# sucaiku.net
KiCad netlist of a schematic drawn in EasyEDA Pro
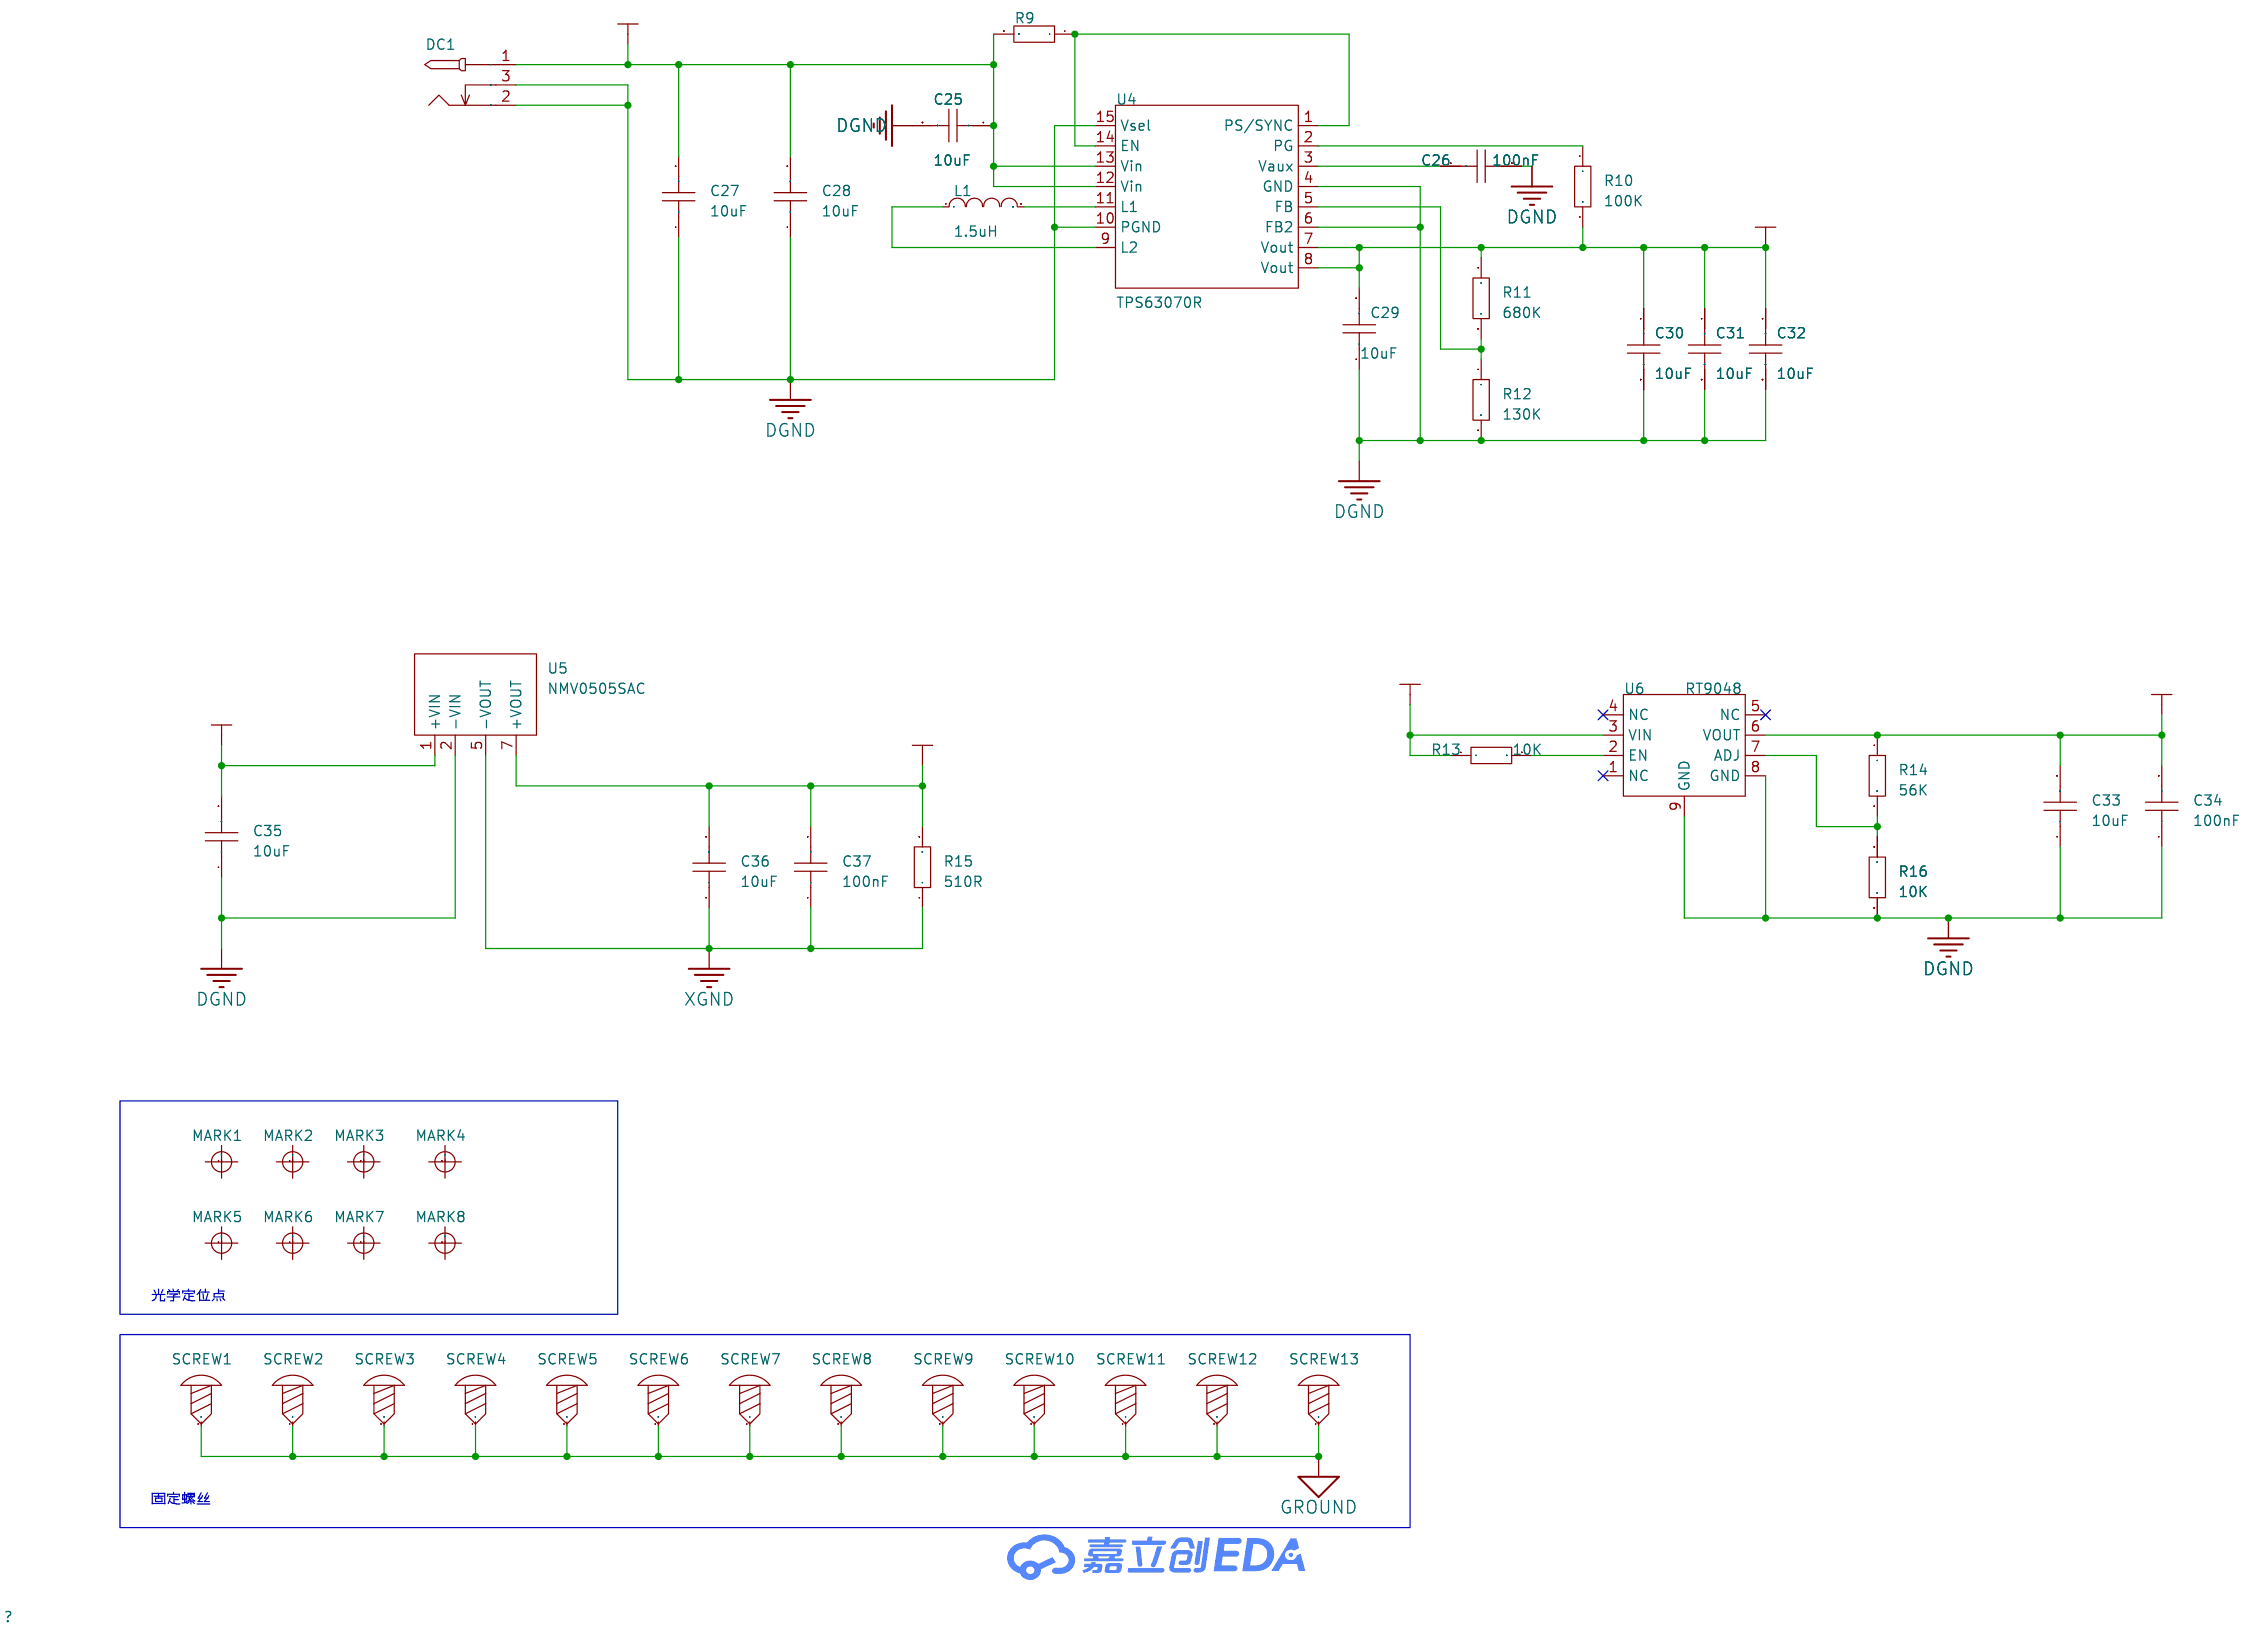
[diagram p0: POWER]
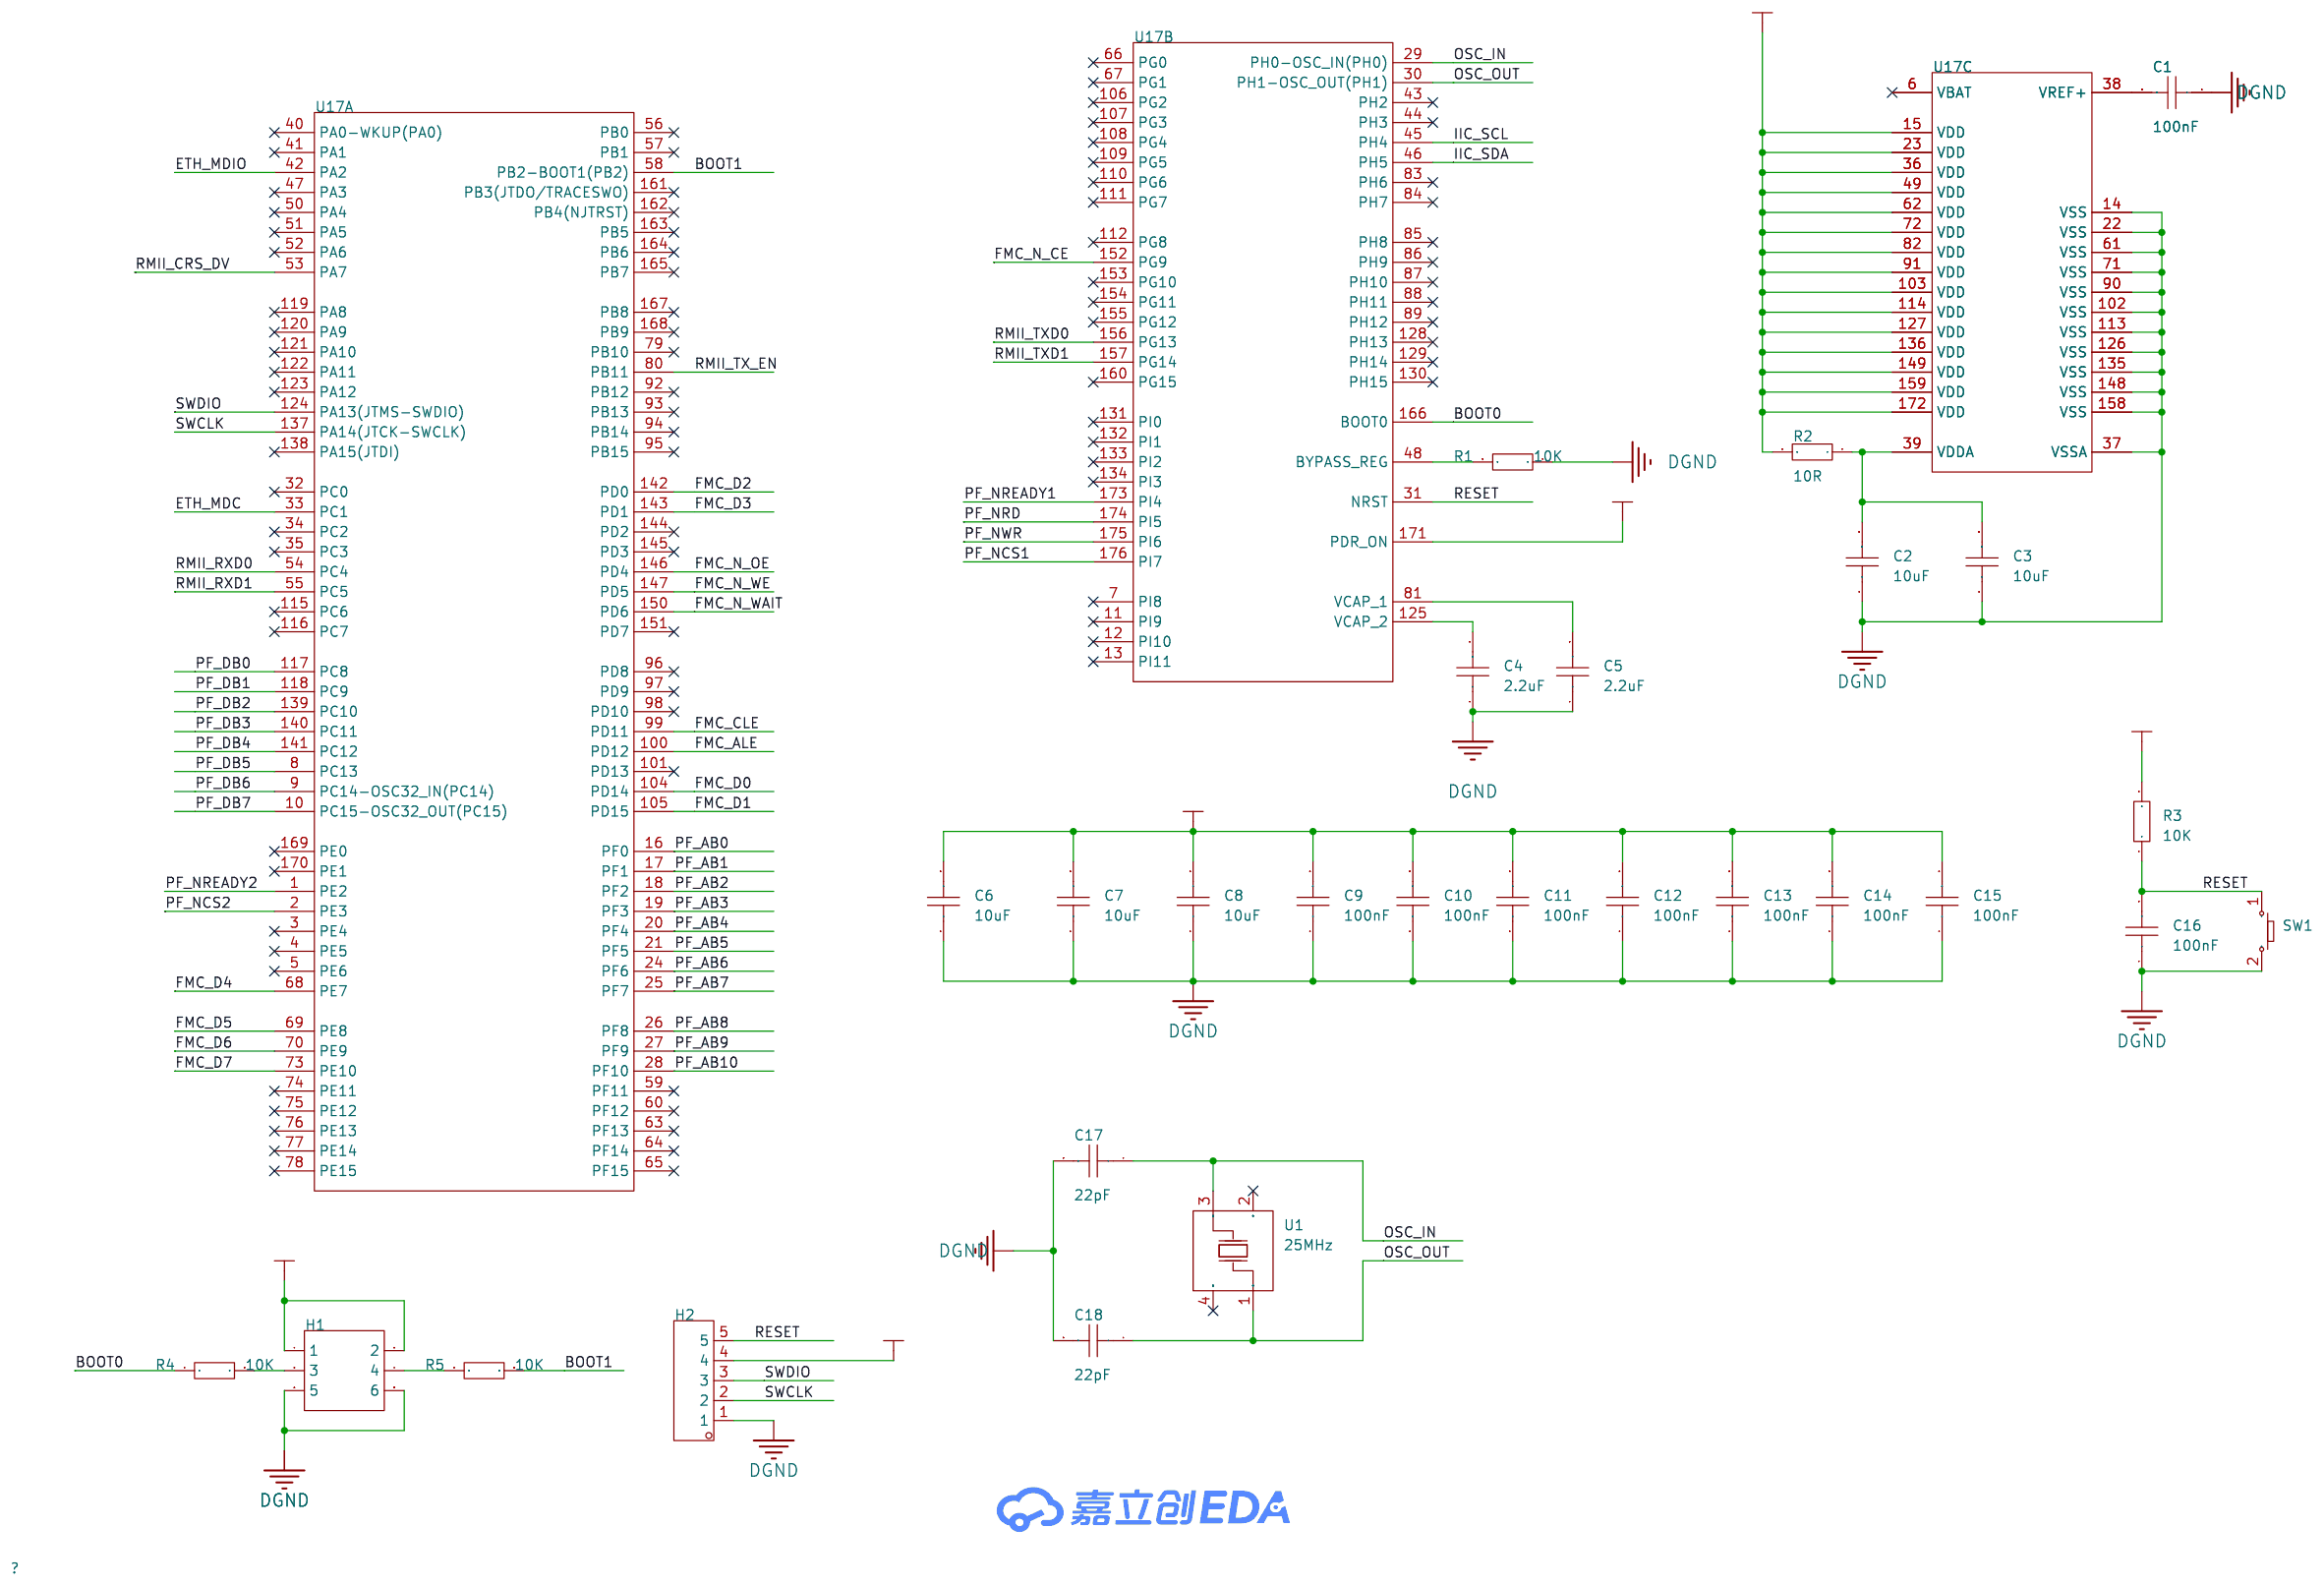
[diagram p1: MCU]
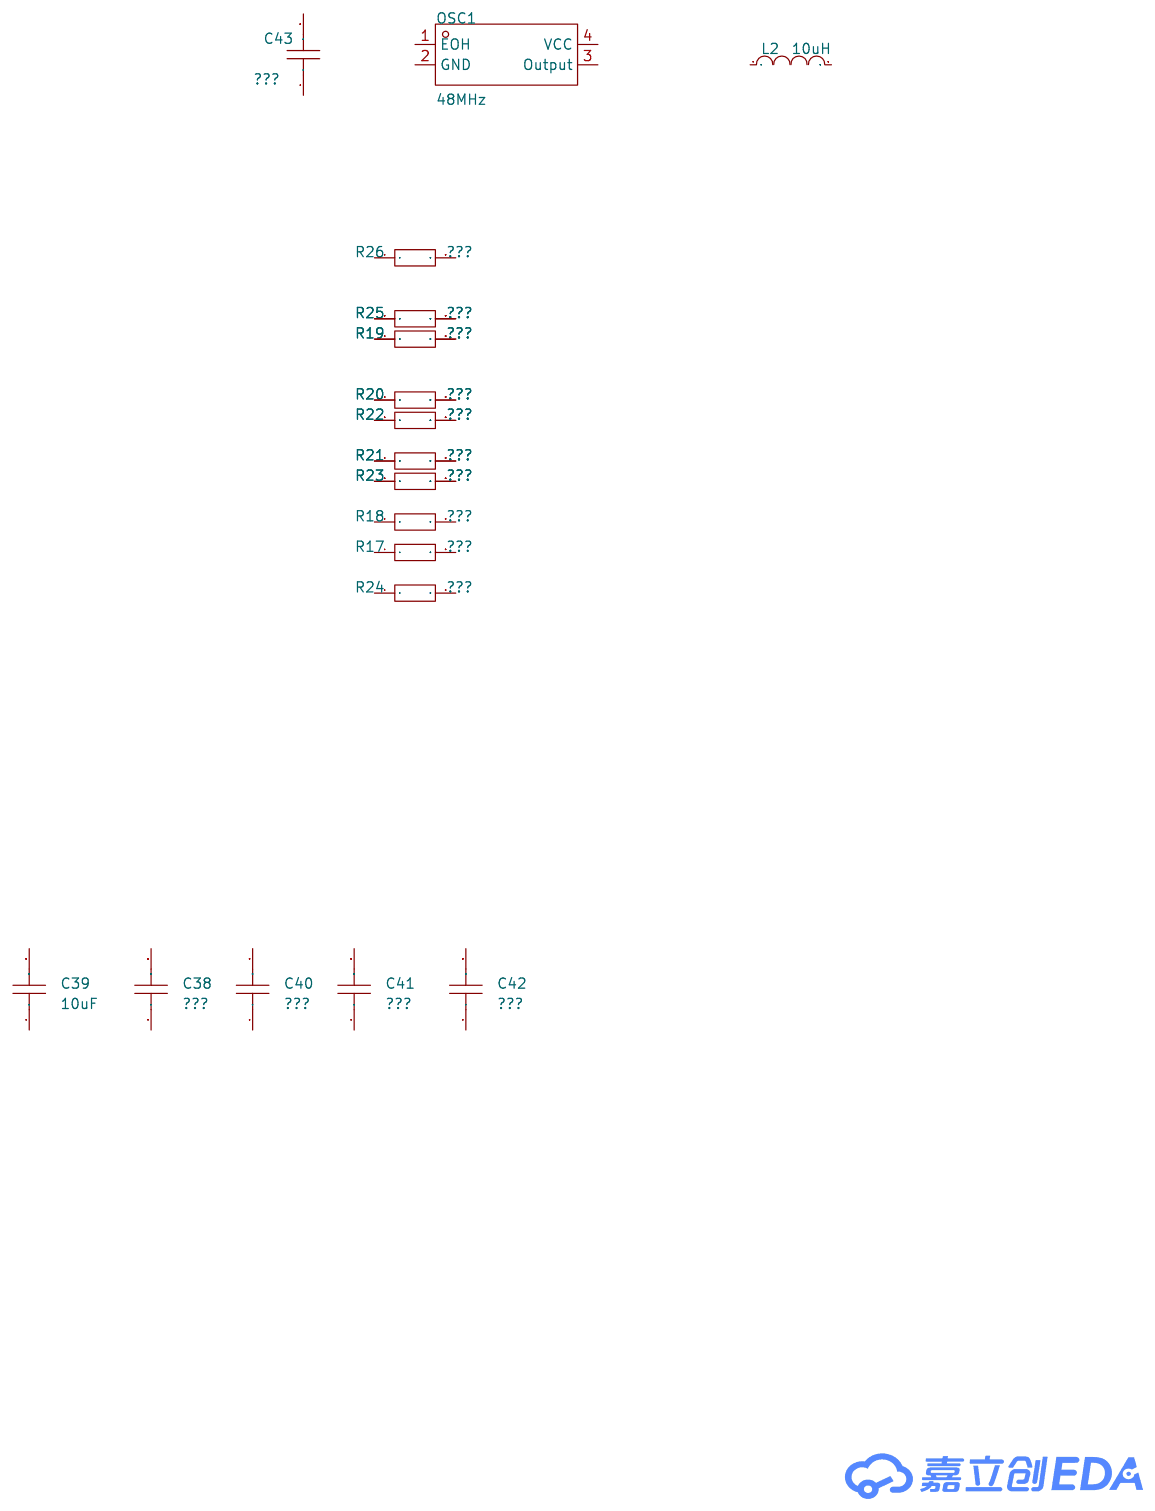
[diagram p2: PROFIBUS1]
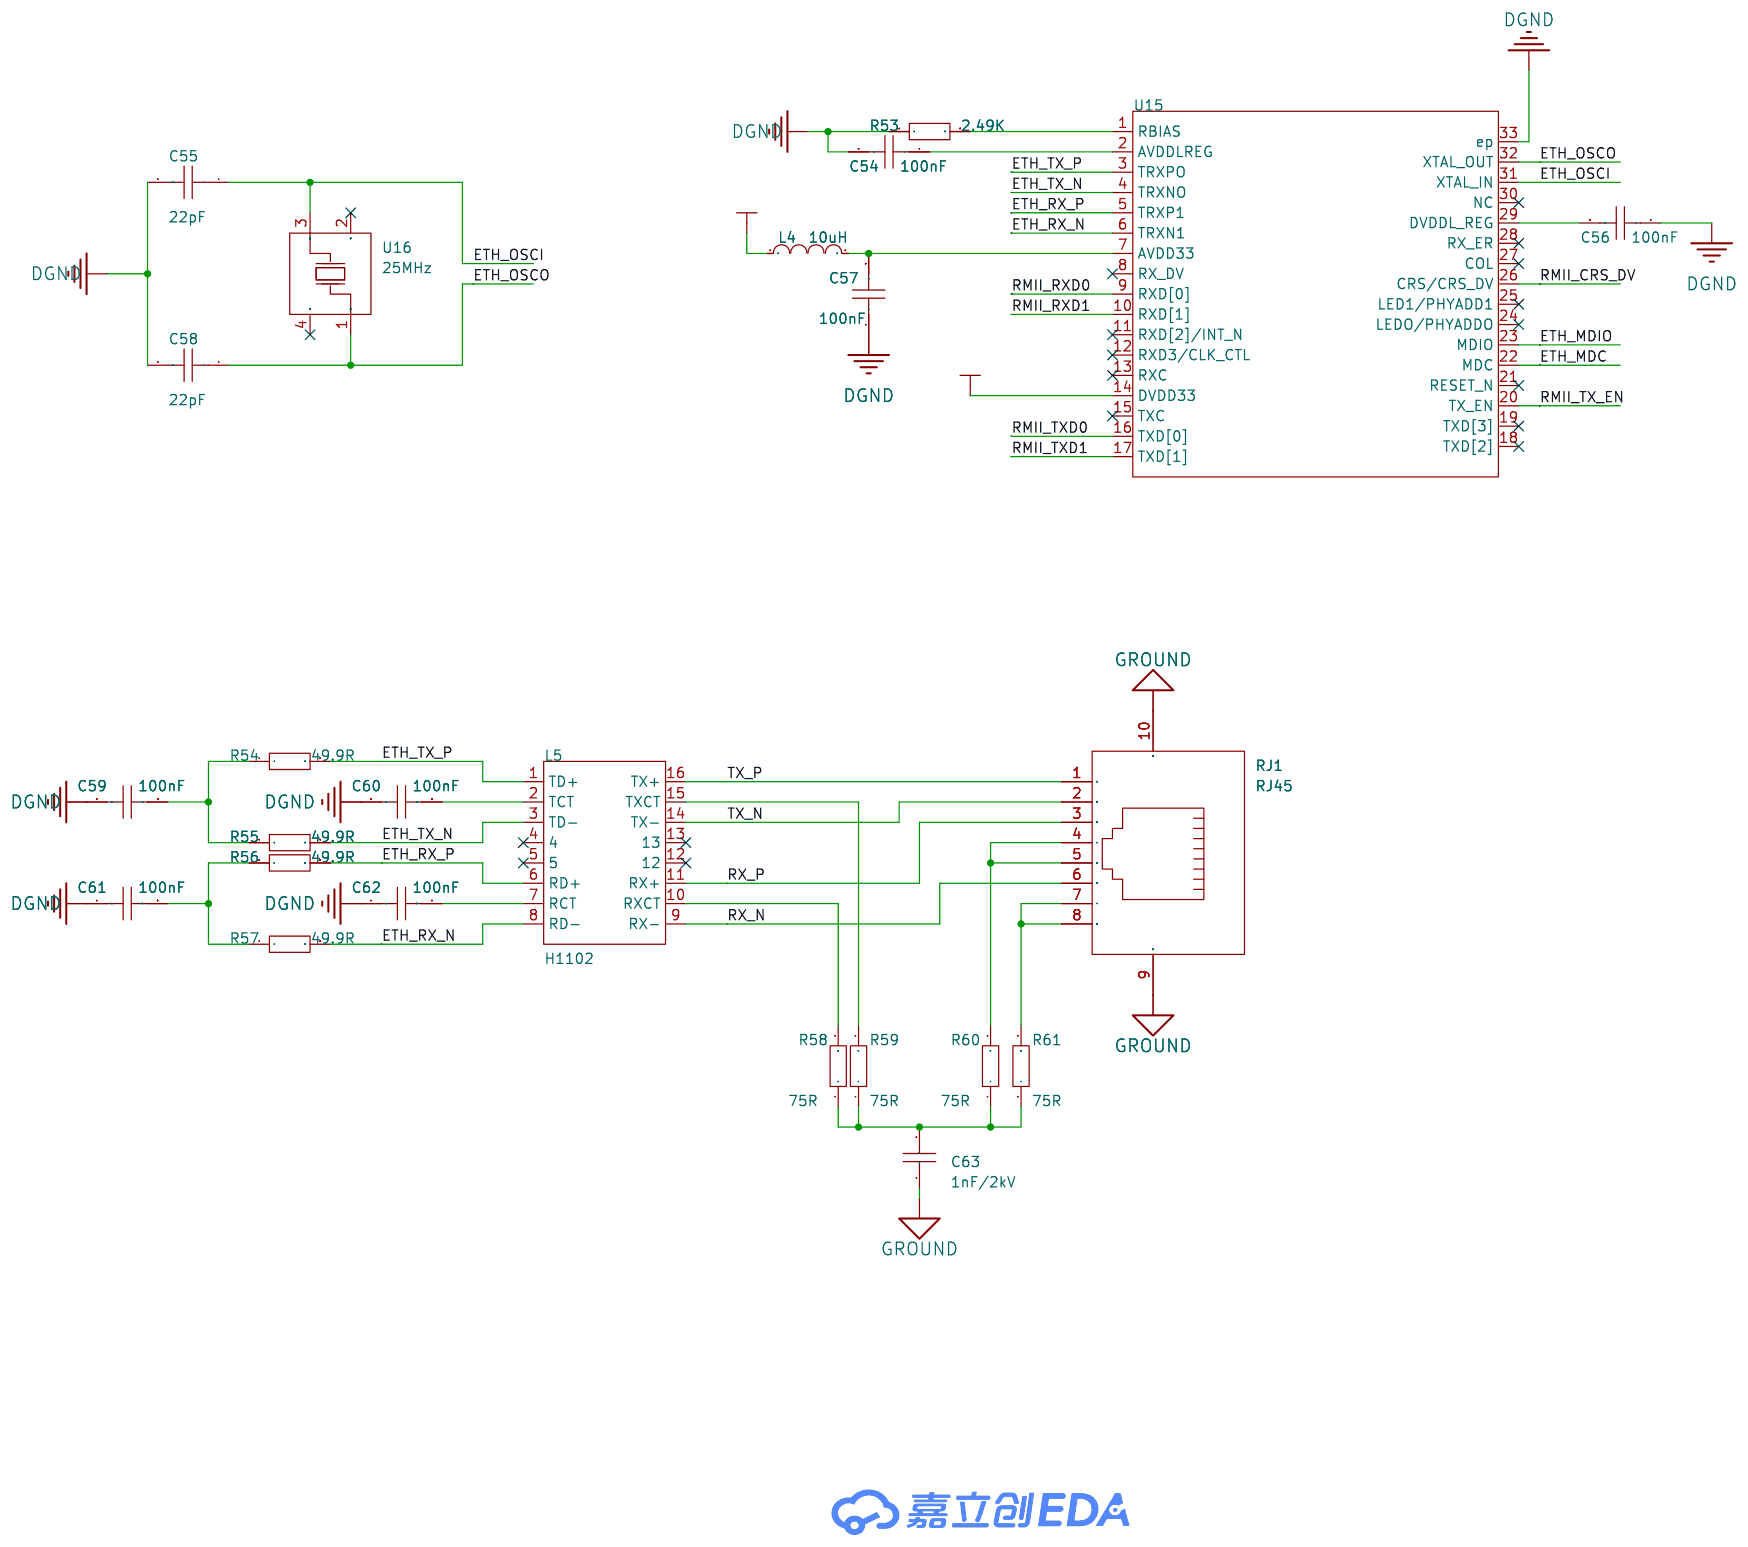
[diagram p3: ETHERNET]
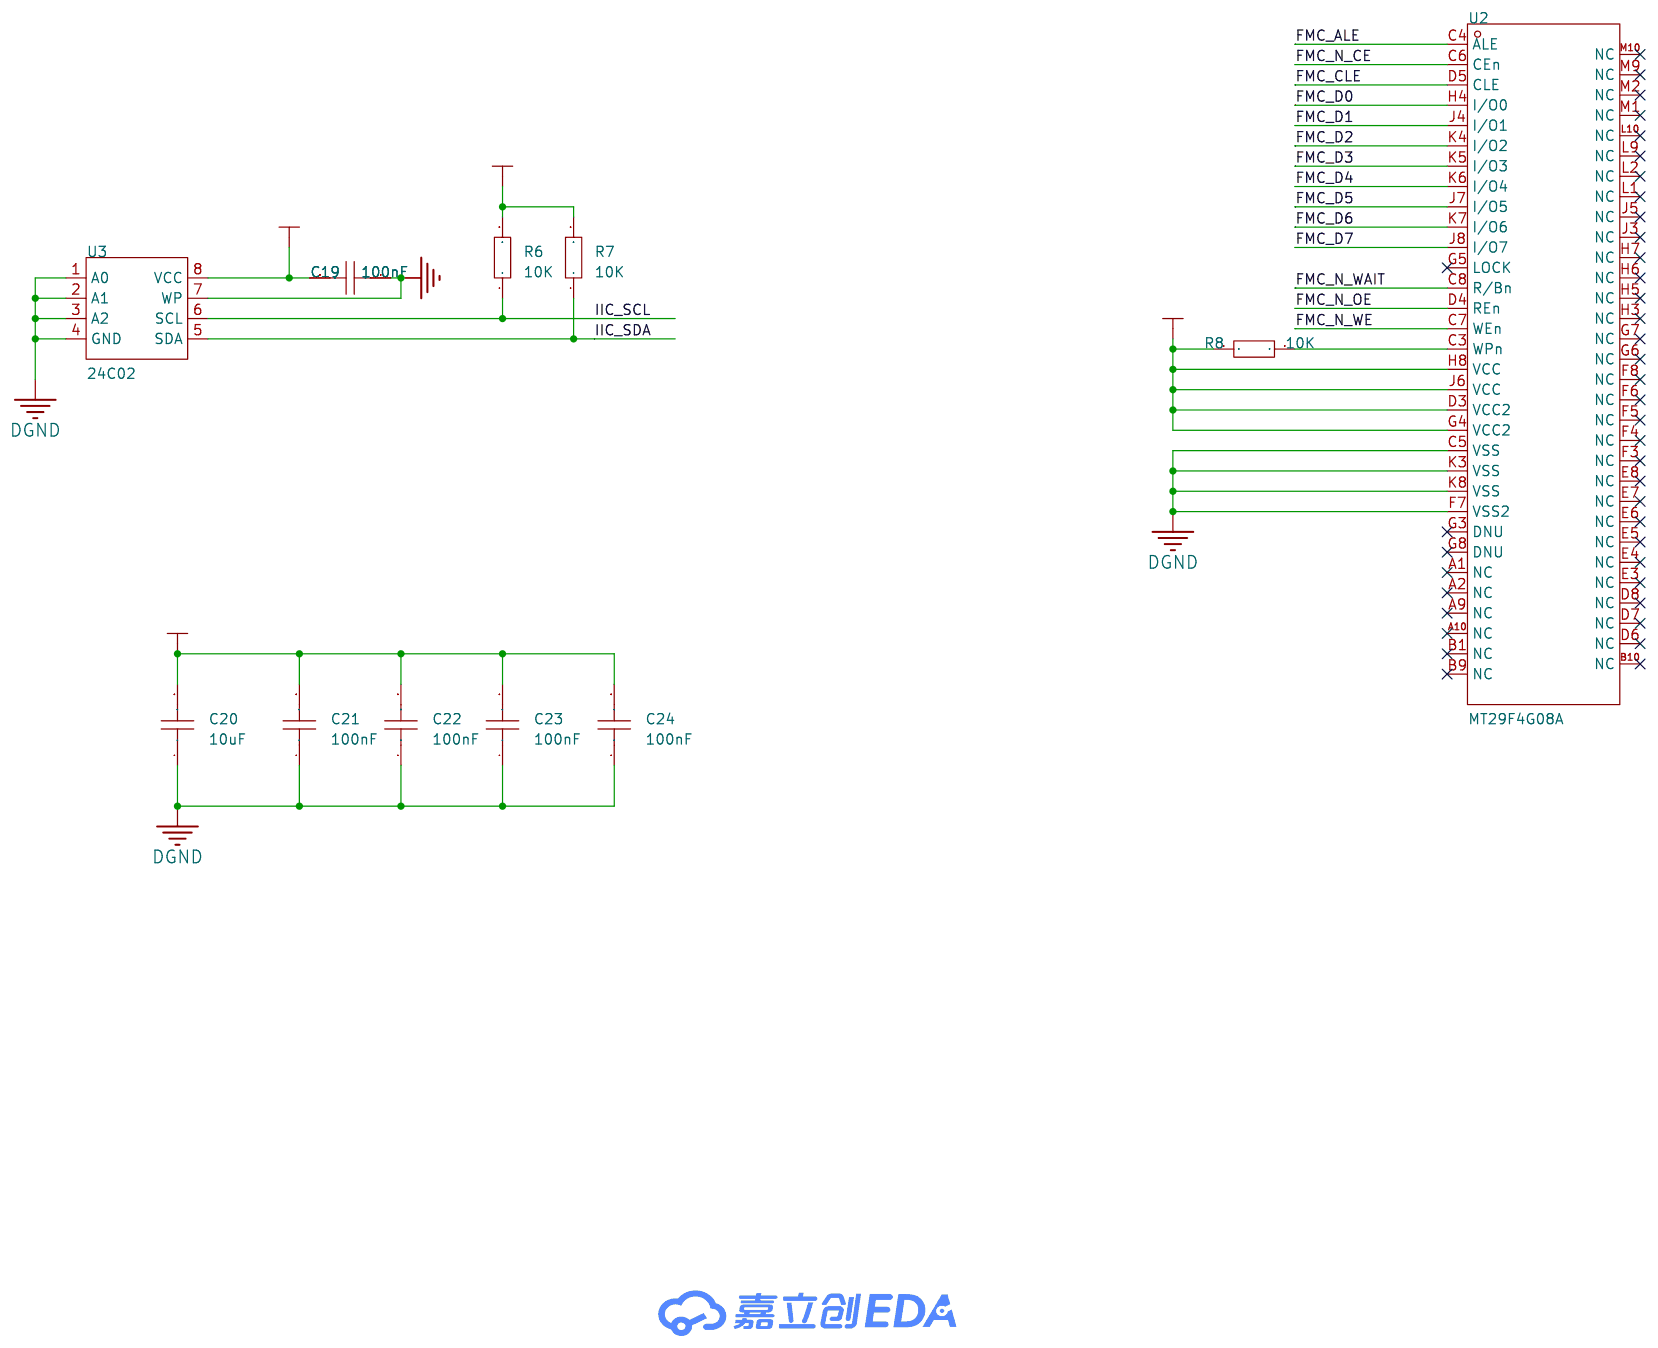
[diagram p4: MEMORY]
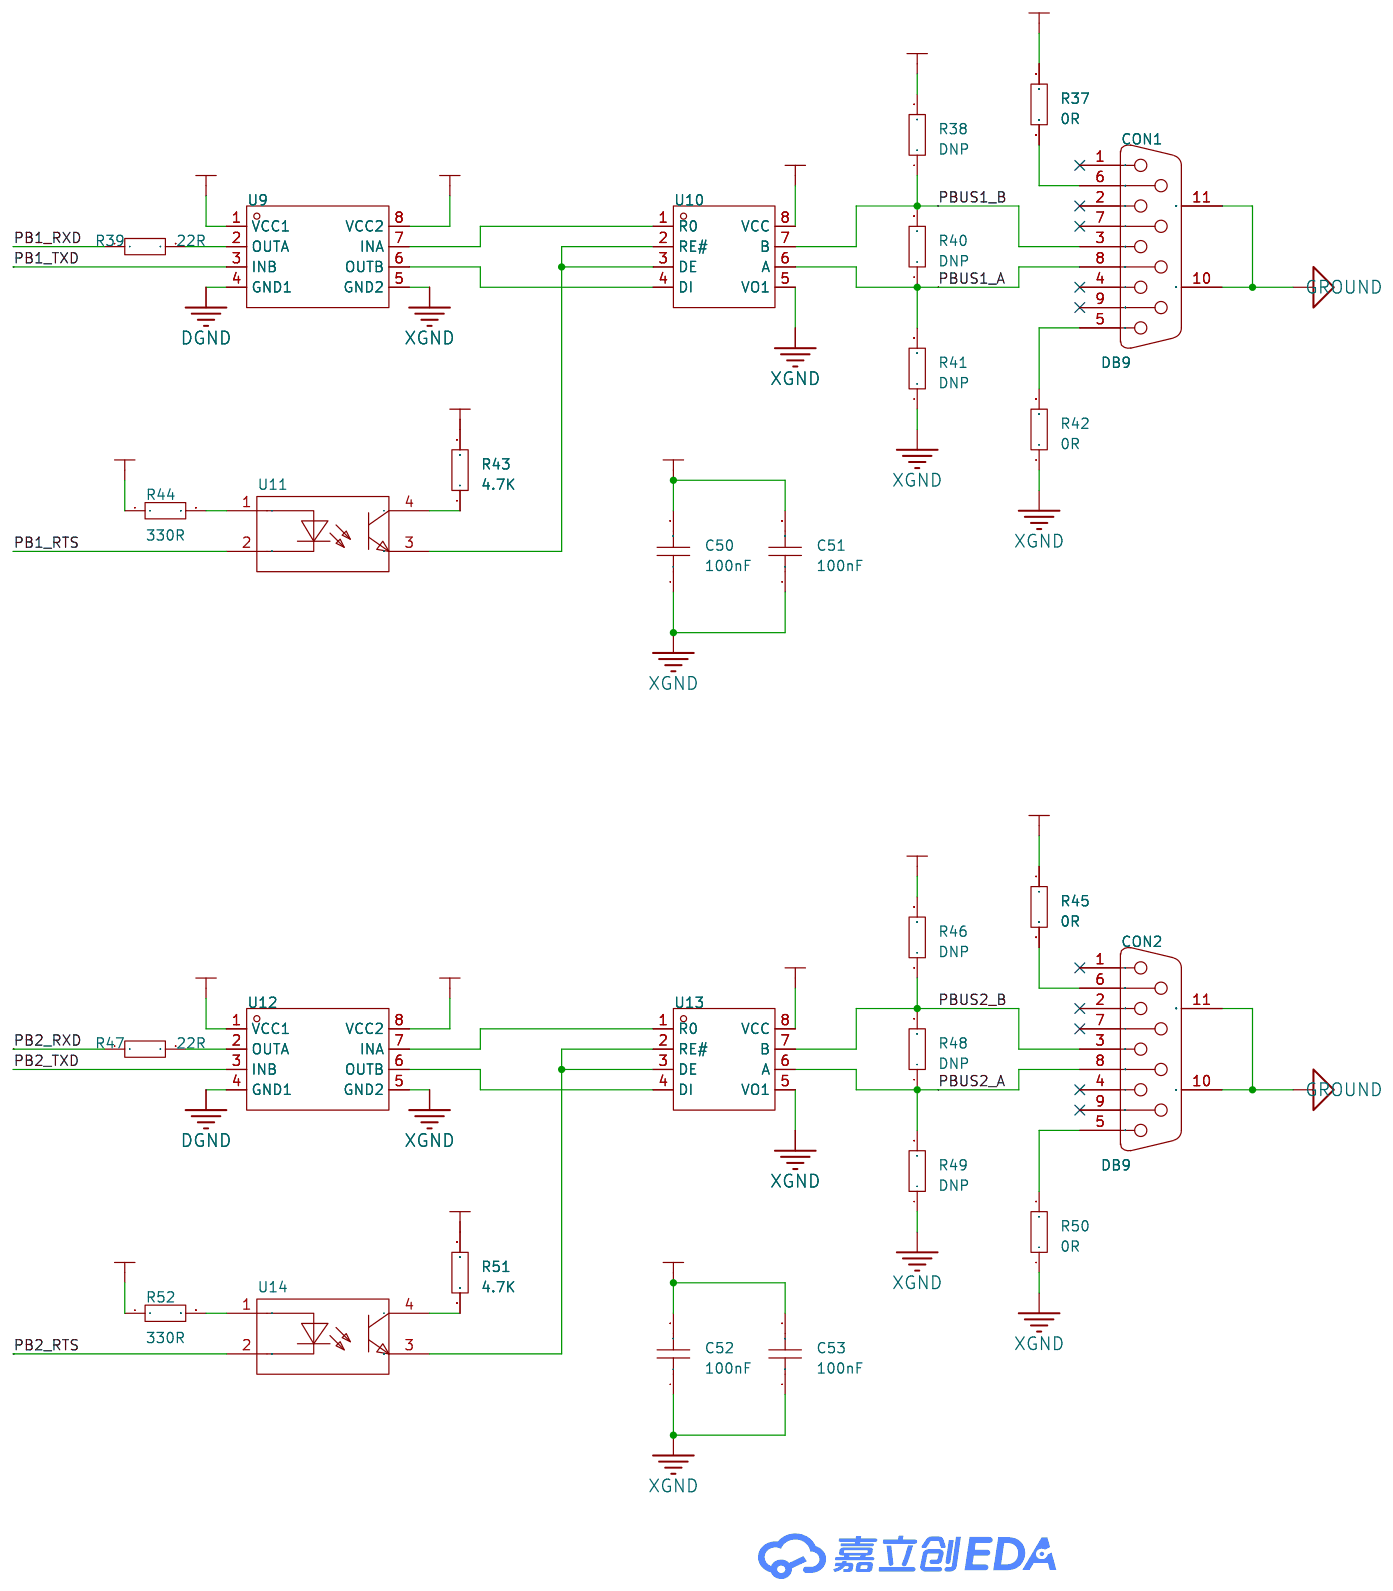
[diagram p5: PROFIBUS2]

(export (version "E")
  (design (tool "Eeschema 10.0.6"))
  (components
    (comp (ref "C25")
      (value "10uF")
      (footprint "easyedapro:C0805")
      (libsource (lib "easyedapro") (part "CapAcitance"))
    )
    (comp (ref "C26")
      (value "100nF")
      (footprint "easyedapro:C0805")
      (libsource (lib "easyedapro") (part "CapAcitance"))
    )
    (comp (ref "C27")
      (value "10uF")
      (footprint "easyedapro:C0805")
      (libsource (lib "easyedapro") (part "CapAcitance"))
    )
    (comp (ref "C28")
      (value "10uF")
      (footprint "easyedapro:C0805")
      (libsource (lib "easyedapro") (part "CapAcitance"))
    )
    (comp (ref "C29")
      (value "10uF")
      (footprint "easyedapro:C0805")
      (libsource (lib "easyedapro") (part "CapAcitance"))
    )
    (comp (ref "C30")
      (value "10uF")
      (footprint "easyedapro:C0805")
      (libsource (lib "easyedapro") (part "CapAcitance"))
    )
    (comp (ref "C31")
      (value "10uF")
      (footprint "easyedapro:C0805")
      (libsource (lib "easyedapro") (part "CapAcitance"))
    )
    (comp (ref "C32")
      (value "10uF")
      (footprint "easyedapro:C0805")
      (libsource (lib "easyedapro") (part "CapAcitance"))
    )
    (comp (ref "C33")
      (value "10uF")
      (footprint "easyedapro:C0805")
      (libsource (lib "easyedapro") (part "CapAcitance"))
    )
    (comp (ref "C34")
      (value "100nF")
      (footprint "easyedapro:C0805")
      (libsource (lib "easyedapro") (part "CapAcitance"))
    )
    (comp (ref "C35")
      (value "10uF")
      (footprint "easyedapro:C0805")
      (libsource (lib "easyedapro") (part "CapAcitance"))
    )
    (comp (ref "C36")
      (value "10uF")
      (footprint "easyedapro:C0805")
      (libsource (lib "easyedapro") (part "CapAcitance"))
    )
    (comp (ref "C37")
      (value "100nF")
      (footprint "easyedapro:C0805")
      (libsource (lib "easyedapro") (part "CapAcitance"))
    )
    (comp (ref "DC1")
      (value "~")
      (footprint "easyedapro:DC-005_2.5")
      (libsource (lib "easyedapro") (part "DC-005_2.5"))
    )
    (comp (ref "L1")
      (value "1.5uH")
      (footprint "easyedapro:IND-SMD_L4.0-W4.0_FNR40XXS")
      (fields (field (name "Manufacturer Part") "FNR4020S1R5MT") (field (name "Manufacturer") "cjiang(长江微电)"))
      (libsource (lib "easyedapro") (part "FNR4020S1R5MT"))
    )
    (comp (ref "MARK1")
      (value "~")
      (footprint "easyedapro:Mark-Point-1mm")
      (description "Mark点")
      (libsource (lib "easyedapro") (part "Mark-Point"))
    )
    (comp (ref "MARK2")
      (value "~")
      (footprint "easyedapro:Mark-Point-1mm")
      (description "Mark点")
      (libsource (lib "easyedapro") (part "Mark-Point"))
    )
    (comp (ref "MARK3")
      (value "~")
      (footprint "easyedapro:Mark-Point-1mm")
      (description "Mark点")
      (libsource (lib "easyedapro") (part "Mark-Point"))
    )
    (comp (ref "MARK4")
      (value "~")
      (footprint "easyedapro:Mark-Point-1mm")
      (description "Mark点")
      (libsource (lib "easyedapro") (part "Mark-Point"))
    )
    (comp (ref "MARK5")
      (value "~")
      (footprint "easyedapro:Mark-Point-1mm")
      (description "Mark点")
      (libsource (lib "easyedapro") (part "Mark-Point"))
    )
    (comp (ref "MARK6")
      (value "~")
      (footprint "easyedapro:Mark-Point-1mm")
      (description "Mark点")
      (libsource (lib "easyedapro") (part "Mark-Point"))
    )
    (comp (ref "MARK7")
      (value "~")
      (footprint "easyedapro:Mark-Point-1mm")
      (description "Mark点")
      (libsource (lib "easyedapro") (part "Mark-Point"))
    )
    (comp (ref "MARK8")
      (value "~")
      (footprint "easyedapro:Mark-Point-1mm")
      (description "Mark点")
      (libsource (lib "easyedapro") (part "Mark-Point"))
    )
    (comp (ref "R9") (value "10K") (footprint "easyedapro:R1206") (libsource (lib "easyedapro") (part "电阻")))
    (comp (ref "R10")
      (value "100K")
      (footprint "easyedapro:R1206")
      (libsource (lib "easyedapro") (part "电阻"))
    )
    (comp (ref "R11")
      (value "680K")
      (footprint "easyedapro:R1206")
      (libsource (lib "easyedapro") (part "电阻"))
    )
    (comp (ref "R12")
      (value "130K")
      (footprint "easyedapro:R1206")
      (libsource (lib "easyedapro") (part "电阻"))
    )
    (comp (ref "R13") (value "10K") (footprint "easyedapro:R1206") (libsource (lib "easyedapro") (part "电阻")))
    (comp (ref "R14") (value "56K") (footprint "easyedapro:R1206") (libsource (lib "easyedapro") (part "电阻")))
    (comp (ref "R15")
      (value "510R")
      (footprint "easyedapro:R1206")
      (libsource (lib "easyedapro") (part "电阻"))
    )
    (comp (ref "R16") (value "10K") (footprint "easyedapro:R1206") (libsource (lib "easyedapro") (part "电阻")))
    (comp (ref "SCREW1")
      (value "~")
      (footprint "easyedapro:M3螺丝")
      (libsource (lib "easyedapro") (part "螺丝孔"))
    )
    (comp (ref "SCREW2")
      (value "~")
      (footprint "easyedapro:M3螺丝")
      (libsource (lib "easyedapro") (part "螺丝孔"))
    )
    (comp (ref "SCREW3")
      (value "~")
      (footprint "easyedapro:M3螺丝")
      (libsource (lib "easyedapro") (part "螺丝孔"))
    )
    (comp (ref "SCREW4")
      (value "~")
      (footprint "easyedapro:M3螺丝")
      (libsource (lib "easyedapro") (part "螺丝孔"))
    )
    (comp (ref "SCREW5")
      (value "~")
      (footprint "easyedapro:M3螺丝")
      (libsource (lib "easyedapro") (part "螺丝孔"))
    )
    (comp (ref "SCREW6")
      (value "~")
      (footprint "easyedapro:M3螺丝")
      (libsource (lib "easyedapro") (part "螺丝孔"))
    )
    (comp (ref "SCREW7")
      (value "~")
      (footprint "easyedapro:M3螺丝")
      (libsource (lib "easyedapro") (part "螺丝孔"))
    )
    (comp (ref "SCREW8")
      (value "~")
      (footprint "easyedapro:M3螺丝")
      (libsource (lib "easyedapro") (part "螺丝孔"))
    )
    (comp (ref "SCREW9")
      (value "~")
      (footprint "easyedapro:M3螺丝")
      (libsource (lib "easyedapro") (part "螺丝孔"))
    )
    (comp (ref "SCREW10")
      (value "~")
      (footprint "easyedapro:M3螺丝")
      (libsource (lib "easyedapro") (part "螺丝孔"))
    )
    (comp (ref "SCREW11")
      (value "~")
      (footprint "easyedapro:M3螺丝")
      (libsource (lib "easyedapro") (part "螺丝孔"))
    )
    (comp (ref "SCREW12")
      (value "~")
      (footprint "easyedapro:M3螺丝")
      (libsource (lib "easyedapro") (part "螺丝孔"))
    )
    (comp (ref "SCREW13")
      (value "~")
      (footprint "easyedapro:M3螺丝")
      (libsource (lib "easyedapro") (part "螺丝孔"))
    )
    (comp (ref "U4")
      (value "TPS63070R")
      (footprint "easyedapro:VQFN-HR-15_L3.0-W2.5-P0.50-BL_TPS63070RNMR")
      (fields (field (name "Manufacturer") "TI(德州仪器)"))
      (libsource (lib "easyedapro") (part "TPS63070RNMR"))
    )
    (comp (ref "U5")
      (value "NMV0505SAC")
      (footprint "easyedapro:PWRM-TH_4P-L19.5-W6.0-P2.54_NMV0505SAC")
      (fields (field (name "Manufacturer") "muRata(村田)"))
      (libsource (lib "easyedapro") (part "NMV0505SAC"))
    )
    (comp (ref "U6")
      (value "RT9048")
      (footprint "easyedapro:ESOP-8_L4.9-W3.9-P1.27-LS6.0-BL-EP")
      (fields (field (name "Manufacturer") "RICHTEK(立锜)"))
      (libsource (lib "easyedapro") (part "RT9048GSP"))
    )
    (comp (ref "C1")
      (value "100nF")
      (footprint "easyedapro:C0805")
      (libsource (lib "easyedapro") (part "CapAcitance"))
    )
    (comp (ref "C2")
      (value "10uF")
      (footprint "easyedapro:C0805")
      (libsource (lib "easyedapro") (part "CapAcitance"))
    )
    (comp (ref "C3")
      (value "10uF")
      (footprint "easyedapro:C0805")
      (libsource (lib "easyedapro") (part "CapAcitance"))
    )
    (comp (ref "C4")
      (value "2.2uF")
      (footprint "easyedapro:C0805")
      (libsource (lib "easyedapro") (part "CapAcitance"))
    )
    (comp (ref "C5")
      (value "2.2uF")
      (footprint "easyedapro:C0805")
      (libsource (lib "easyedapro") (part "CapAcitance"))
    )
    (comp (ref "C6")
      (value "10uF")
      (footprint "easyedapro:C0805")
      (libsource (lib "easyedapro") (part "CapAcitance"))
    )
    (comp (ref "C7")
      (value "10uF")
      (footprint "easyedapro:C0805")
      (libsource (lib "easyedapro") (part "CapAcitance"))
    )
    (comp (ref "C8")
      (value "10uF")
      (footprint "easyedapro:C0805")
      (libsource (lib "easyedapro") (part "CapAcitance"))
    )
    (comp (ref "C9")
      (value "100nF")
      (footprint "easyedapro:C0805")
      (libsource (lib "easyedapro") (part "CapAcitance"))
    )
    (comp (ref "C10")
      (value "100nF")
      (footprint "easyedapro:C0805")
      (libsource (lib "easyedapro") (part "CapAcitance"))
    )
    (comp (ref "C11")
      (value "100nF")
      (footprint "easyedapro:C0805")
      (libsource (lib "easyedapro") (part "CapAcitance"))
    )
    (comp (ref "C12")
      (value "100nF")
      (footprint "easyedapro:C0805")
      (libsource (lib "easyedapro") (part "CapAcitance"))
    )
    (comp (ref "C13")
      (value "100nF")
      (footprint "easyedapro:C0805")
      (libsource (lib "easyedapro") (part "CapAcitance"))
    )
    (comp (ref "C14")
      (value "100nF")
      (footprint "easyedapro:C0805")
      (libsource (lib "easyedapro") (part "CapAcitance"))
    )
    (comp (ref "C15")
      (value "100nF")
      (footprint "easyedapro:C0805")
      (libsource (lib "easyedapro") (part "CapAcitance"))
    )
    (comp (ref "C16")
      (value "100nF")
      (footprint "easyedapro:C0805")
      (libsource (lib "easyedapro") (part "CapAcitance"))
    )
    (comp (ref "C17")
      (value "22pF")
      (footprint "easyedapro:C0805")
      (libsource (lib "easyedapro") (part "CapAcitance"))
    )
    (comp (ref "C18")
      (value "22pF")
      (footprint "easyedapro:C0805")
      (libsource (lib "easyedapro") (part "CapAcitance"))
    )
    (comp (ref "H1")
      (value "~")
      (footprint "easyedapro:HDR-TH_6P-P2.54-V-R2-C3-S2.54_A2541WV-2X3P")
      (libsource (lib "easyedapro") (part "HDR-M-2.54_2x3"))
    )
    (comp (ref "H2")
      (value "~")
      (footprint "easyedapro:HDR-TH_5P-P2.54-V-M")
      (libsource (lib "easyedapro") (part "MTP125-1105S1"))
    )
    (comp (ref "R1") (value "10K") (footprint "easyedapro:R1206") (libsource (lib "easyedapro") (part "电阻")))
    (comp (ref "R2") (value "10R") (footprint "easyedapro:R1206") (libsource (lib "easyedapro") (part "电阻")))
    (comp (ref "R3") (value "10K") (footprint "easyedapro:R1206") (libsource (lib "easyedapro") (part "电阻")))
    (comp (ref "R4") (value "10K") (footprint "easyedapro:R1206") (libsource (lib "easyedapro") (part "电阻")))
    (comp (ref "R5") (value "10K") (footprint "easyedapro:R1206") (libsource (lib "easyedapro") (part "电阻")))
    (comp (ref "SW1")
      (value "~")
      (footprint "easyedapro:Key_SMD_3x4x2")
      (libsource (lib "easyedapro") (part "轻触按键x2"))
    )
    (comp (ref "U1")
      (value "25MHz")
      (footprint "easyedapro:CRYSTAL-SMD_4P-L3.2-W2.5-TR")
      (libsource (lib "easyedapro") (part "25MHZ"))
    )
    (comp (ref "U17")
      (value "STM32F429IGT6")
      (footprint "easyedapro:LQFP-176_L24.0-W24.0-P0.50-LS26.0-BL")
      (fields (field (name "Manufacturer") "ST(意法半导体)"))
      (libsource (lib "easyedapro") (part "STM32F429IGT6"))
    )
    (comp (ref "C38")
      (value "???")
      (footprint "easyedapro:C0805")
      (libsource (lib "easyedapro") (part "CapAcitance"))
    )
    (comp (ref "C39")
      (value "10uF")
      (footprint "easyedapro:C0805")
      (libsource (lib "easyedapro") (part "CapAcitance"))
    )
    (comp (ref "C40")
      (value "???")
      (footprint "easyedapro:C0805")
      (libsource (lib "easyedapro") (part "CapAcitance"))
    )
    (comp (ref "C41")
      (value "???")
      (footprint "easyedapro:C0805")
      (libsource (lib "easyedapro") (part "CapAcitance"))
    )
    (comp (ref "C42")
      (value "???")
      (footprint "easyedapro:C0805")
      (libsource (lib "easyedapro") (part "CapAcitance"))
    )
    (comp (ref "C43")
      (value "???")
      (footprint "easyedapro:C0805")
      (libsource (lib "easyedapro") (part "CapAcitance"))
    )
    (comp (ref "L2")
      (value "10uH")
      (footprint "easyedapro:L0402")
      (libsource (lib "easyedapro") (part "SDCL1005C10NJTDFM01"))
    )
    (comp (ref "OSC1")
      (value "48MHz")
      (footprint "easyedapro:OSC-SMD_4P-L2.0-W1.6-BL")
      (description "频率:48MHz;输出模式:HCMOS；TTL;工作电压:2.5V;供电电流:15mA;")
      (fields (field (name "Manufacturer Part") "CA20C4805INT") (field (name "Manufacturer") "CTS(西迪斯)"))
      (libsource (lib "easyedapro") (part "CA20C4805INT"))
    )
    (comp (ref "R17") (value "???") (footprint "easyedapro:R1206") (libsource (lib "easyedapro") (part "电阻")))
    (comp (ref "R18") (value "???") (footprint "easyedapro:R1206") (libsource (lib "easyedapro") (part "电阻")))
    (comp (ref "R19") (value "???") (footprint "easyedapro:R1206") (libsource (lib "easyedapro") (part "电阻")))
    (comp (ref "R20") (value "???") (footprint "easyedapro:R1206") (libsource (lib "easyedapro") (part "电阻")))
    (comp (ref "R21") (value "???") (footprint "easyedapro:R1206") (libsource (lib "easyedapro") (part "电阻")))
    (comp (ref "R22") (value "???") (footprint "easyedapro:R1206") (libsource (lib "easyedapro") (part "电阻")))
    (comp (ref "R23") (value "???") (footprint "easyedapro:R1206") (libsource (lib "easyedapro") (part "电阻")))
    (comp (ref "R24") (value "???") (footprint "easyedapro:R1206") (libsource (lib "easyedapro") (part "电阻")))
    (comp (ref "R25") (value "???") (footprint "easyedapro:R1206") (libsource (lib "easyedapro") (part "电阻")))
    (comp (ref "R26") (value "???") (footprint "easyedapro:R1206") (libsource (lib "easyedapro") (part "电阻")))
    (comp (ref "C54")
      (value "100nF")
      (footprint "easyedapro:C0805")
      (libsource (lib "easyedapro") (part "CapAcitance"))
    )
    (comp (ref "C55")
      (value "22pF")
      (footprint "easyedapro:C0805")
      (libsource (lib "easyedapro") (part "CapAcitance"))
    )
    (comp (ref "C56")
      (value "100nF")
      (footprint "easyedapro:C0805")
      (libsource (lib "easyedapro") (part "CapAcitance"))
    )
    (comp (ref "C57")
      (value "100nF")
      (footprint "easyedapro:C0805")
      (libsource (lib "easyedapro") (part "CapAcitance"))
    )
    (comp (ref "C58")
      (value "22pF")
      (footprint "easyedapro:C0805")
      (libsource (lib "easyedapro") (part "CapAcitance"))
    )
    (comp (ref "C59")
      (value "100nF")
      (footprint "easyedapro:C0805")
      (libsource (lib "easyedapro") (part "CapAcitance"))
    )
    (comp (ref "C60")
      (value "100nF")
      (footprint "easyedapro:C0805")
      (libsource (lib "easyedapro") (part "CapAcitance"))
    )
    (comp (ref "C61")
      (value "100nF")
      (footprint "easyedapro:C0805")
      (libsource (lib "easyedapro") (part "CapAcitance"))
    )
    (comp (ref "C62")
      (value "100nF")
      (footprint "easyedapro:C0805")
      (libsource (lib "easyedapro") (part "CapAcitance"))
    )
    (comp (ref "C63")
      (value "1nF/2kV")
      (footprint "easyedapro:C1206")
      (fields (field (name "Manufacturer Part") "1206B102K202NT") (field (name "Manufacturer") "FH(风华)"))
      (libsource (lib "easyedapro") (part "1206B102K202NT"))
    )
    (comp (ref "L4")
      (value "10uH")
      (footprint "easyedapro:L0402")
      (libsource (lib "easyedapro") (part "SDCL1005C10NJTDFM01"))
    )
    (comp (ref "L5")
      (value "H1102")
      (footprint "easyedapro:XFMR-SMD_H1102N")
      (fields (field (name "Manufacturer Part") "H1102N") (field (name "Manufacturer") "CND-tek(磁联达)"))
      (libsource (lib "easyedapro") (part "H1102N"))
    )
    (comp (ref "R53")
      (value "2.49K")
      (footprint "easyedapro:R1206")
      (libsource (lib "easyedapro") (part "电阻"))
    )
    (comp (ref "R54")
      (value "49.9R")
      (footprint "easyedapro:R1206")
      (libsource (lib "easyedapro") (part "电阻"))
    )
    (comp (ref "R55")
      (value "49.9R")
      (footprint "easyedapro:R1206")
      (libsource (lib "easyedapro") (part "电阻"))
    )
    (comp (ref "R56")
      (value "49.9R")
      (footprint "easyedapro:R1206")
      (libsource (lib "easyedapro") (part "电阻"))
    )
    (comp (ref "R57")
      (value "49.9R")
      (footprint "easyedapro:R1206")
      (libsource (lib "easyedapro") (part "电阻"))
    )
    (comp (ref "R58") (value "75R") (footprint "easyedapro:R1206") (libsource (lib "easyedapro") (part "电阻")))
    (comp (ref "R59") (value "75R") (footprint "easyedapro:R1206") (libsource (lib "easyedapro") (part "电阻")))
    (comp (ref "R60") (value "75R") (footprint "easyedapro:R1206") (libsource (lib "easyedapro") (part "电阻")))
    (comp (ref "R61") (value "75R") (footprint "easyedapro:R1206") (libsource (lib "easyedapro") (part "电阻")))
    (comp (ref "RJ1")
      (value "RJ45")
      (footprint "easyedapro:RJ45-TH_R-RJ45R10P-B000-1")
      (libsource (lib "easyedapro") (part "RJ45-9758-1"))
    )
    (comp (ref "U15")
      (value "YT8512C")
      (footprint "easyedapro:QFN-32_L5.0-W5.0-P0.50-BL-EP3.4")
      (libsource (lib "easyedapro") (part "YT8512C"))
    )
    (comp (ref "U16")
      (value "25MHz")
      (footprint "easyedapro:CRYSTAL-SMD_4P-L3.2-W2.5-TR")
      (libsource (lib "easyedapro") (part "25MHZ"))
    )
    (comp (ref "C19")
      (value "100nF")
      (footprint "easyedapro:C0805")
      (libsource (lib "easyedapro") (part "CapAcitance"))
    )
    (comp (ref "C20")
      (value "10uF")
      (footprint "easyedapro:C0805")
      (libsource (lib "easyedapro") (part "CapAcitance"))
    )
    (comp (ref "C21")
      (value "100nF")
      (footprint "easyedapro:C0805")
      (libsource (lib "easyedapro") (part "CapAcitance"))
    )
    (comp (ref "C22")
      (value "100nF")
      (footprint "easyedapro:C0805")
      (libsource (lib "easyedapro") (part "CapAcitance"))
    )
    (comp (ref "C23")
      (value "100nF")
      (footprint "easyedapro:C0805")
      (libsource (lib "easyedapro") (part "CapAcitance"))
    )
    (comp (ref "C24")
      (value "100nF")
      (footprint "easyedapro:C0805")
      (libsource (lib "easyedapro") (part "CapAcitance"))
    )
    (comp (ref "R6") (value "10K") (footprint "easyedapro:R1206") (libsource (lib "easyedapro") (part "电阻")))
    (comp (ref "R7") (value "10K") (footprint "easyedapro:R1206") (libsource (lib "easyedapro") (part "电阻")))
    (comp (ref "R8") (value "10K") (footprint "easyedapro:R1206") (libsource (lib "easyedapro") (part "电阻")))
    (comp (ref "U2")
      (value "MT29F4G08A")
      (footprint "easyedapro:VFBGA-63_L11.0-W9.0-P0.80-BL_MT29F2G08ABAEAH4-IT-E")
      (libsource (lib "easyedapro") (part "MT29F4G08A"))
    )
    (comp (ref "U3")
      (value "24C02")
      (footprint "easyedapro:SOP-8_L4.9-W3.9-P1.27-LS6.0-BL")
      (fields (field (name "Manufacturer") "HX(恒佳兴)"))
      (libsource (lib "easyedapro") (part "24C02"))
    )
    (comp (ref "C50")
      (value "100nF")
      (footprint "easyedapro:C0805")
      (libsource (lib "easyedapro") (part "CapAcitance"))
    )
    (comp (ref "C51")
      (value "100nF")
      (footprint "easyedapro:C0805")
      (libsource (lib "easyedapro") (part "CapAcitance"))
    )
    (comp (ref "C52")
      (value "100nF")
      (footprint "easyedapro:C0805")
      (libsource (lib "easyedapro") (part "CapAcitance"))
    )
    (comp (ref "C53")
      (value "100nF")
      (footprint "easyedapro:C0805")
      (libsource (lib "easyedapro") (part "CapAcitance"))
    )
    (comp (ref "CON1")
      (value "DB9")
      (footprint "easyedapro:DB9-TH_DT10121-M5N3-4F")
      (libsource (lib "easyedapro") (part "DB9 TH90"))
    )
    (comp (ref "CON2")
      (value "DB9")
      (footprint "easyedapro:DB9-TH_DT10121-M5N3-4F")
      (libsource (lib "easyedapro") (part "DB9 TH90"))
    )
    (comp (ref "R37") (value "0R") (footprint "easyedapro:R1206") (libsource (lib "easyedapro") (part "电阻")))
    (comp (ref "R38") (value "DNP") (footprint "easyedapro:R1206") (libsource (lib "easyedapro") (part "电阻")))
    (comp (ref "R39") (value "22R") (footprint "easyedapro:R1206") (libsource (lib "easyedapro") (part "电阻")))
    (comp (ref "R40") (value "DNP") (footprint "easyedapro:R1206") (libsource (lib "easyedapro") (part "电阻")))
    (comp (ref "R41") (value "DNP") (footprint "easyedapro:R1206") (libsource (lib "easyedapro") (part "电阻")))
    (comp (ref "R42") (value "0R") (footprint "easyedapro:R1206") (libsource (lib "easyedapro") (part "电阻")))
    (comp (ref "R43")
      (value "4.7K")
      (footprint "easyedapro:R1206")
      (libsource (lib "easyedapro") (part "电阻"))
    )
    (comp (ref "R44")
      (value "330R")
      (footprint "easyedapro:R1206")
      (libsource (lib "easyedapro") (part "电阻"))
    )
    (comp (ref "R45") (value "0R") (footprint "easyedapro:R1206") (libsource (lib "easyedapro") (part "电阻")))
    (comp (ref "R46") (value "DNP") (footprint "easyedapro:R1206") (libsource (lib "easyedapro") (part "电阻")))
    (comp (ref "R47") (value "22R") (footprint "easyedapro:R1206") (libsource (lib "easyedapro") (part "电阻")))
    (comp (ref "R48") (value "DNP") (footprint "easyedapro:R1206") (libsource (lib "easyedapro") (part "电阻")))
    (comp (ref "R49") (value "DNP") (footprint "easyedapro:R1206") (libsource (lib "easyedapro") (part "电阻")))
    (comp (ref "R50") (value "0R") (footprint "easyedapro:R1206") (libsource (lib "easyedapro") (part "电阻")))
    (comp (ref "R51")
      (value "4.7K")
      (footprint "easyedapro:R1206")
      (libsource (lib "easyedapro") (part "电阻"))
    )
    (comp (ref "R52")
      (value "330R")
      (footprint "easyedapro:R1206")
      (libsource (lib "easyedapro") (part "电阻"))
    )
    (comp (ref "U9")
      (value "ISO7221AD")
      (footprint "easyedapro:SOIC-8_L5.0-W4.0-P1.27-LS6.0-BL")
      (fields (field (name "Manufacturer") "TI(德州仪器)"))
      (libsource (lib "easyedapro") (part "ISO7221AD"))
    )
    (comp (ref "U10")
      (value "RS485")
      (footprint "easyedapro:SOP-8_L4.9-W3.9-P1.27-LS6.0-BL")
      (fields (field (name "Manufacturer") "GR(国睿)"))
      (libsource (lib "easyedapro") (part "RS485"))
    )
    (comp (ref "U11")
      (value "TLP781(GR-TP6,F)")
      (footprint "easyedapro:SOP-4_L6.5-W4.6-P2.54-LS10.3-TL")
      (fields (field (name "Manufacturer") "TOSHIBA(东芝)"))
      (libsource (lib "easyedapro") (part "TLP781(GR-TP6，F)"))
    )
    (comp (ref "U12")
      (value "ISO7221AD")
      (footprint "easyedapro:SOIC-8_L5.0-W4.0-P1.27-LS6.0-BL")
      (fields (field (name "Manufacturer") "TI(德州仪器)"))
      (libsource (lib "easyedapro") (part "ISO7221AD"))
    )
    (comp (ref "U13")
      (value "RS485")
      (footprint "easyedapro:SOP-8_L4.9-W3.9-P1.27-LS6.0-BL")
      (fields (field (name "Manufacturer") "GR(国睿)"))
      (libsource (lib "easyedapro") (part "RS485"))
    )
    (comp (ref "U14")
      (value "TLP781(GR-TP6,F)")
      (footprint "easyedapro:SOP-4_L6.5-W4.6-P2.54-LS10.3-TL")
      (fields (field (name "Manufacturer") "TOSHIBA(东芝)"))
      (libsource (lib "easyedapro") (part "TLP781(GR-TP6，F)"))
    )
  )
  (nets
    (net (code "1") (name "BOOT0") (class "Default")
      (node (ref "R4") (pin "1") (pinfunction "1_1") (pintype "input"))
      (node (ref "U17") (pin "166") (pinfunction "BOOT0_166") (pintype "unspecified"))
    )
    (net (code "2") (name "BOOT1") (class "Default")
      (node (ref "R5") (pin "2") (pinfunction "2_2") (pintype "input"))
      (node (ref "U17") (pin "58") (pinfunction "PB2-BOOT1(PB2)_58") (pintype "unspecified"))
    )
    (net (code "3") (name "DGND") (class "Default")
      (node (ref "C1") (pin "1") (pinfunction "1_1") (pintype "input"))
      (node (ref "C10") (pin "1") (pinfunction "1_1") (pintype "input"))
      (node (ref "C11") (pin "1") (pinfunction "1_1") (pintype "input"))
      (node (ref "C12") (pin "1") (pinfunction "1_1") (pintype "input"))
      (node (ref "C13") (pin "1") (pinfunction "1_1") (pintype "input"))
      (node (ref "C14") (pin "1") (pinfunction "1_1") (pintype "input"))
      (node (ref "C15") (pin "1") (pinfunction "1_1") (pintype "input"))
      (node (ref "C16") (pin "1") (pinfunction "1_1") (pintype "input"))
      (node (ref "C17") (pin "2") (pinfunction "2_2") (pintype "input"))
      (node (ref "C18") (pin "2") (pinfunction "2_2") (pintype "input"))
      (node (ref "C19") (pin "1") (pinfunction "1_1") (pintype "input"))
      (node (ref "C2") (pin "1") (pinfunction "1_1") (pintype "input"))
      (node (ref "C20") (pin "1") (pinfunction "1_1") (pintype "input"))
      (node (ref "C21") (pin "1") (pinfunction "1_1") (pintype "input"))
      (node (ref "C22") (pin "1") (pinfunction "1_1") (pintype "input"))
      (node (ref "C23") (pin "1") (pinfunction "1_1") (pintype "input"))
      (node (ref "C24") (pin "1") (pinfunction "1_1") (pintype "input"))
      (node (ref "C25") (pin "2") (pinfunction "2_2") (pintype "input"))
      (node (ref "C26") (pin "2") (pinfunction "2_2") (pintype "input"))
      (node (ref "C27") (pin "1") (pinfunction "1_1") (pintype "input"))
      (node (ref "C28") (pin "1") (pinfunction "1_1") (pintype "input"))
      (node (ref "C29") (pin "1") (pinfunction "1_1") (pintype "input"))
      (node (ref "C3") (pin "1") (pinfunction "1_1") (pintype "input"))
      (node (ref "C30") (pin "2") (pinfunction "2_2") (pintype "input"))
      (node (ref "C31") (pin "2") (pinfunction "2_2") (pintype "input"))
      (node (ref "C32") (pin "2") (pinfunction "2_2") (pintype "input"))
      (node (ref "C33") (pin "1") (pinfunction "1_1") (pintype "input"))
      (node (ref "C34") (pin "1") (pinfunction "1_1") (pintype "input"))
      (node (ref "C35") (pin "1") (pinfunction "1_1") (pintype "input"))
      (node (ref "C4") (pin "1") (pinfunction "1_1") (pintype "input"))
      (node (ref "C5") (pin "1") (pinfunction "1_1") (pintype "input"))
      (node (ref "C54") (pin "2") (pinfunction "2_2") (pintype "input"))
      (node (ref "C55") (pin "2") (pinfunction "2_2") (pintype "input"))
      (node (ref "C56") (pin "1") (pinfunction "1_1") (pintype "input"))
      (node (ref "C57") (pin "1") (pinfunction "1_1") (pintype "input"))
      (node (ref "C58") (pin "2") (pinfunction "2_2") (pintype "input"))
      (node (ref "C59") (pin "1") (pinfunction "1_1") (pintype "input"))
      (node (ref "C6") (pin "1") (pinfunction "1_1") (pintype "input"))
      (node (ref "C60") (pin "1") (pinfunction "1_1") (pintype "input"))
      (node (ref "C61") (pin "1") (pinfunction "1_1") (pintype "input"))
      (node (ref "C62") (pin "1") (pinfunction "1_1") (pintype "input"))
      (node (ref "C7") (pin "1") (pinfunction "1_1") (pintype "input"))
      (node (ref "C8") (pin "1") (pinfunction "1_1") (pintype "input"))
      (node (ref "C9") (pin "1") (pinfunction "1_1") (pintype "input"))
      (node (ref "DC1") (pin "2") (pinfunction "2_2") (pintype "input"))
      (node (ref "DC1") (pin "3") (pinfunction "3_3") (pintype "input"))
      (node (ref "H1") (pin "5") (pinfunction "5_5") (pintype "input"))
      (node (ref "H1") (pin "6") (pinfunction "6_6") (pintype "input"))
      (node (ref "H2") (pin "1") (pinfunction "1_1") (pintype "unspecified"))
      (node (ref "R1") (pin "1") (pinfunction "1_1") (pintype "input"))
      (node (ref "R12") (pin "2") (pinfunction "2_2") (pintype "input"))
      (node (ref "R16") (pin "2") (pinfunction "2_2") (pintype "input"))
      (node (ref "R53") (pin "1") (pinfunction "1_1") (pintype "input"))
      (node (ref "SW1") (pin "2") (pinfunction "2_2") (pintype "input"))
      (node (ref "U12") (pin "4") (pinfunction "GND1_4") (pintype "unspecified"))
      (node (ref "U15") (pin "33") (pinfunction "ep_33") (pintype "unspecified"))
      (node (ref "U17") (pin "102") (pinfunction "VSS_102") (pintype "unspecified"))
      (node (ref "U17") (pin "113") (pinfunction "VSS_113") (pintype "unspecified"))
      (node (ref "U17") (pin "126") (pinfunction "VSS_126") (pintype "unspecified"))
      (node (ref "U17") (pin "135") (pinfunction "VSS_135") (pintype "unspecified"))
      (node (ref "U17") (pin "14") (pinfunction "VSS_14") (pintype "unspecified"))
      (node (ref "U17") (pin "148") (pinfunction "VSS_148") (pintype "unspecified"))
      (node (ref "U17") (pin "158") (pinfunction "VSS_158") (pintype "unspecified"))
      (node (ref "U17") (pin "22") (pinfunction "VSS_22") (pintype "unspecified"))
      (node (ref "U17") (pin "37") (pinfunction "VSSA_37") (pintype "unspecified"))
      (node (ref "U17") (pin "61") (pinfunction "VSS_61") (pintype "unspecified"))
      (node (ref "U17") (pin "71") (pinfunction "VSS_71") (pintype "unspecified"))
      (node (ref "U17") (pin "90") (pinfunction "VSS_90") (pintype "unspecified"))
      (node (ref "U2") (pin "C5") (pinfunction "VSS_C5") (pintype "unspecified"))
      (node (ref "U2") (pin "F7") (pinfunction "VSS2_F7") (pintype "unspecified"))
      (node (ref "U2") (pin "K3") (pinfunction "VSS_K3") (pintype "unspecified"))
      (node (ref "U2") (pin "K8") (pinfunction "VSS_K8") (pintype "unspecified"))
      (node (ref "U3") (pin "1") (pinfunction "A0_1") (pintype "unspecified"))
      (node (ref "U3") (pin "2") (pinfunction "A1_2") (pintype "unspecified"))
      (node (ref "U3") (pin "3") (pinfunction "A2_3") (pintype "unspecified"))
      (node (ref "U3") (pin "4") (pinfunction "GND_4") (pintype "unspecified"))
      (node (ref "U3") (pin "7") (pinfunction "WP_7") (pintype "unspecified"))
      (node (ref "U4") (pin "10") (pinfunction "PGND_10") (pintype "unspecified"))
      (node (ref "U4") (pin "15") (pinfunction "Vsel_15") (pintype "unspecified"))
      (node (ref "U4") (pin "4") (pinfunction "GND_4") (pintype "unspecified"))
      (node (ref "U4") (pin "6") (pinfunction "FB2_6") (pintype "unspecified"))
      (node (ref "U5") (pin "2") (pinfunction "-VIN_2") (pintype "unspecified"))
      (node (ref "U6") (pin "8") (pinfunction "GND_8") (pintype "unspecified"))
      (node (ref "U6") (pin "9") (pinfunction "GND_9") (pintype "unspecified"))
      (node (ref "U9") (pin "4") (pinfunction "GND1_4") (pintype "unspecified"))
    )
    (net (code "4") (name "ETH_MDC") (class "Default")
      (node (ref "U15") (pin "22") (pinfunction "MDC_22") (pintype "unspecified"))
      (node (ref "U17") (pin "33") (pinfunction "PC1_33") (pintype "unspecified"))
    )
    (net (code "5") (name "ETH_MDIO") (class "Default")
      (node (ref "U15") (pin "23") (pinfunction "MDIO_23") (pintype "unspecified"))
      (node (ref "U17") (pin "42") (pinfunction "PA2_42") (pintype "unspecified"))
    )
    (net (code "6") (name "ETH_OSCI") (class "Default")
      (node (ref "C55") (pin "1") (pinfunction "1_1") (pintype "input"))
      (node (ref "U15") (pin "31") (pinfunction "XTAL_IN_31") (pintype "unspecified"))
      (node (ref "U16") (pin "3") (pinfunction "OSC2_3") (pintype "unspecified"))
    )
    (net (code "7") (name "ETH_OSCO") (class "Default")
      (node (ref "C58") (pin "1") (pinfunction "1_1") (pintype "input"))
      (node (ref "U15") (pin "32") (pinfunction "XTAL_OUT_32") (pintype "unspecified"))
      (node (ref "U16") (pin "1") (pinfunction "OSC1_1") (pintype "unspecified"))
    )
    (net (code "8") (name "ETH_RX_N") (class "Default")
      (node (ref "L5") (pin "8") (pinfunction "RD-_8") (pintype "unspecified"))
      (node (ref "R57") (pin "2") (pinfunction "2_2") (pintype "input"))
      (node (ref "U15") (pin "6") (pinfunction "TRXN1_6") (pintype "unspecified"))
    )
    (net (code "9") (name "ETH_RX_P") (class "Default")
      (node (ref "L5") (pin "6") (pinfunction "RD+_6") (pintype "unspecified"))
      (node (ref "R56") (pin "2") (pinfunction "2_2") (pintype "input"))
      (node (ref "U15") (pin "5") (pinfunction "TRXP1_5") (pintype "unspecified"))
    )
    (net (code "10") (name "ETH_TX_N") (class "Default")
      (node (ref "L5") (pin "3") (pinfunction "TD-_3") (pintype "unspecified"))
      (node (ref "R55") (pin "2") (pinfunction "2_2") (pintype "input"))
      (node (ref "U15") (pin "4") (pinfunction "TRXNO_4") (pintype "unspecified"))
    )
    (net (code "11") (name "ETH_TX_P") (class "Default")
      (node (ref "L5") (pin "1") (pinfunction "TD+_1") (pintype "unspecified"))
      (node (ref "R54") (pin "2") (pinfunction "2_2") (pintype "input"))
      (node (ref "U15") (pin "3") (pinfunction "TRXPO_3") (pintype "unspecified"))
    )
    (net (code "12") (name "FMC_ALE") (class "Default")
      (node (ref "U17") (pin "100") (pinfunction "PD12_100") (pintype "unspecified"))
      (node (ref "U2") (pin "C4") (pinfunction "ALE_C4") (pintype "unspecified"))
    )
    (net (code "13") (name "FMC_CLE") (class "Default")
      (node (ref "U17") (pin "99") (pinfunction "PD11_99") (pintype "unspecified"))
      (node (ref "U2") (pin "D5") (pinfunction "CLE_D5") (pintype "unspecified"))
    )
    (net (code "14") (name "FMC_D0") (class "Default")
      (node (ref "U17") (pin "104") (pinfunction "PD14_104") (pintype "unspecified"))
      (node (ref "U2") (pin "H4") (pinfunction "I/O0_H4") (pintype "unspecified"))
    )
    (net (code "15") (name "FMC_D1") (class "Default")
      (node (ref "U17") (pin "105") (pinfunction "PD15_105") (pintype "unspecified"))
      (node (ref "U2") (pin "J4") (pinfunction "I/O1_J4") (pintype "unspecified"))
    )
    (net (code "16") (name "FMC_D2") (class "Default")
      (node (ref "U17") (pin "142") (pinfunction "PD0_142") (pintype "unspecified"))
      (node (ref "U2") (pin "K4") (pinfunction "I/O2_K4") (pintype "unspecified"))
    )
    (net (code "17") (name "FMC_D3") (class "Default")
      (node (ref "U17") (pin "143") (pinfunction "PD1_143") (pintype "unspecified"))
      (node (ref "U2") (pin "K5") (pinfunction "I/O3_K5") (pintype "unspecified"))
    )
    (net (code "18") (name "FMC_D4") (class "Default")
      (node (ref "U17") (pin "68") (pinfunction "PE7_68") (pintype "unspecified"))
      (node (ref "U2") (pin "K6") (pinfunction "I/O4_K6") (pintype "unspecified"))
    )
    (net (code "19") (name "FMC_D5") (class "Default")
      (node (ref "U17") (pin "69") (pinfunction "PE8_69") (pintype "unspecified"))
      (node (ref "U2") (pin "J7") (pinfunction "I/O5_J7") (pintype "unspecified"))
    )
    (net (code "20") (name "FMC_D6") (class "Default")
      (node (ref "U17") (pin "70") (pinfunction "PE9_70") (pintype "unspecified"))
      (node (ref "U2") (pin "K7") (pinfunction "I/O6_K7") (pintype "unspecified"))
    )
    (net (code "21") (name "FMC_D7") (class "Default")
      (node (ref "U17") (pin "73") (pinfunction "PE10_73") (pintype "unspecified"))
      (node (ref "U2") (pin "J8") (pinfunction "I/O7_J8") (pintype "unspecified"))
    )
    (net (code "22") (name "FMC_N_CE") (class "Default")
      (node (ref "U17") (pin "152") (pinfunction "PG9_152") (pintype "unspecified"))
      (node (ref "U2") (pin "C6") (pinfunction "CEn_C6") (pintype "unspecified"))
    )
    (net (code "23") (name "FMC_N_OE") (class "Default")
      (node (ref "U17") (pin "146") (pinfunction "PD4_146") (pintype "unspecified"))
      (node (ref "U2") (pin "D4") (pinfunction "REn_D4") (pintype "unspecified"))
    )
    (net (code "24") (name "FMC_N_WAIT") (class "Default")
      (node (ref "U17") (pin "150") (pinfunction "PD6_150") (pintype "unspecified"))
      (node (ref "U2") (pin "C8") (pinfunction "R/Bn_C8") (pintype "unspecified"))
    )
    (net (code "25") (name "FMC_N_WE") (class "Default")
      (node (ref "U17") (pin "147") (pinfunction "PD5_147") (pintype "unspecified"))
      (node (ref "U2") (pin "C7") (pinfunction "WEn_C7") (pintype "unspecified"))
    )
    (net (code "26") (name "GROUND") (class "Default")
      (node (ref "C63") (pin "1") (pinfunction "1_1") (pintype "input"))
      (node (ref "CON1") (pin "10") (pinfunction "MH1_10") (pintype "input"))
      (node (ref "CON1") (pin "11") (pinfunction "MH2_11") (pintype "input"))
      (node (ref "CON2") (pin "10") (pinfunction "MH1_10") (pintype "input"))
      (node (ref "CON2") (pin "11") (pinfunction "MH2_11") (pintype "input"))
      (node (ref "RJ1") (pin "10") (pinfunction "10_10") (pintype "unspecified"))
      (node (ref "RJ1") (pin "9") (pinfunction "9_9") (pintype "unspecified"))
      (node (ref "SCREW1") (pin "1") (pinfunction "1_1") (pintype "input"))
      (node (ref "SCREW10") (pin "1") (pinfunction "1_1") (pintype "input"))
      (node (ref "SCREW11") (pin "1") (pinfunction "1_1") (pintype "input"))
      (node (ref "SCREW12") (pin "1") (pinfunction "1_1") (pintype "input"))
      (node (ref "SCREW13") (pin "1") (pinfunction "1_1") (pintype "input"))
      (node (ref "SCREW2") (pin "1") (pinfunction "1_1") (pintype "input"))
      (node (ref "SCREW3") (pin "1") (pinfunction "1_1") (pintype "input"))
      (node (ref "SCREW4") (pin "1") (pinfunction "1_1") (pintype "input"))
      (node (ref "SCREW5") (pin "1") (pinfunction "1_1") (pintype "input"))
      (node (ref "SCREW6") (pin "1") (pinfunction "1_1") (pintype "input"))
      (node (ref "SCREW7") (pin "1") (pinfunction "1_1") (pintype "input"))
      (node (ref "SCREW8") (pin "1") (pinfunction "1_1") (pintype "input"))
      (node (ref "SCREW9") (pin "1") (pinfunction "1_1") (pintype "input"))
    )
    (net (code "27") (name "IIC_SCL") (class "Default")
      (node (ref "R6") (pin "1") (pinfunction "1_1") (pintype "input"))
      (node (ref "U17") (pin "45") (pinfunction "PH4_45") (pintype "unspecified"))
      (node (ref "U3") (pin "6") (pinfunction "SCL_6") (pintype "unspecified"))
    )
    (net (code "28") (name "IIC_SDA") (class "Default")
      (node (ref "R7") (pin "1") (pinfunction "1_1") (pintype "input"))
      (node (ref "U17") (pin "46") (pinfunction "PH5_46") (pintype "unspecified"))
      (node (ref "U3") (pin "5") (pinfunction "SDA_5") (pintype "unspecified"))
    )
    (net (code "29") (name "Net-(C59-Pad2)") (class "Default")
      (node (ref "C59") (pin "2") (pinfunction "2_2") (pintype "input"))
      (node (ref "R54") (pin "1") (pinfunction "1_1") (pintype "input"))
      (node (ref "R55") (pin "1") (pinfunction "1_1") (pintype "input"))
    )
    (net (code "30") (name "Net-(C61-Pad2)") (class "Default")
      (node (ref "C61") (pin "2") (pinfunction "2_2") (pintype "input"))
      (node (ref "R56") (pin "1") (pinfunction "1_1") (pintype "input"))
      (node (ref "R57") (pin "1") (pinfunction "1_1") (pintype "input"))
    )
    (net (code "31") (name "Net-(C63-Pad2)") (class "Default")
      (node (ref "C63") (pin "2") (pinfunction "2_2") (pintype "input"))
      (node (ref "R58") (pin "1") (pinfunction "1_1") (pintype "input"))
      (node (ref "R59") (pin "1") (pinfunction "1_1") (pintype "input"))
      (node (ref "R60") (pin "1") (pinfunction "1_1") (pintype "input"))
      (node (ref "R61") (pin "1") (pinfunction "1_1") (pintype "input"))
    )
    (net (code "32") (name "Net-(CON1-Pad5)") (class "Default")
      (node (ref "CON1") (pin "5") (pinfunction "5_5") (pintype "input"))
      (node (ref "R42") (pin "2") (pinfunction "2_2") (pintype "input"))
    )
    (net (code "33") (name "Net-(CON1-Pad6)") (class "Default")
      (node (ref "CON1") (pin "6") (pinfunction "6_6") (pintype "input"))
      (node (ref "R37") (pin "2") (pinfunction "2_2") (pintype "input"))
    )
    (net (code "34") (name "Net-(CON2-Pad5)") (class "Default")
      (node (ref "CON2") (pin "5") (pinfunction "5_5") (pintype "input"))
      (node (ref "R50") (pin "2") (pinfunction "2_2") (pintype "input"))
    )
    (net (code "35") (name "Net-(CON2-Pad6)") (class "Default")
      (node (ref "CON2") (pin "6") (pinfunction "6_6") (pintype "input"))
      (node (ref "R45") (pin "2") (pinfunction "2_2") (pintype "input"))
    )
    (net (code "36") (name "Net-(H1-Pad3)") (class "Default")
      (node (ref "H1") (pin "3") (pinfunction "3_3") (pintype "input"))
      (node (ref "R4") (pin "2") (pinfunction "2_2") (pintype "input"))
    )
    (net (code "37") (name "Net-(H1-Pad4)") (class "Default")
      (node (ref "H1") (pin "4") (pinfunction "4_4") (pintype "input"))
      (node (ref "R5") (pin "1") (pinfunction "1_1") (pintype "input"))
    )
    (net (code "38") (name "Net-(L5-RCT)") (class "Default")
      (node (ref "C62") (pin "2") (pinfunction "2_2") (pintype "input"))
      (node (ref "L5") (pin "7") (pinfunction "RCT_7") (pintype "unspecified"))
    )
    (net (code "39") (name "Net-(L5-RXCT)") (class "Default")
      (node (ref "L5") (pin "10") (pinfunction "RXCT_10") (pintype "unspecified"))
      (node (ref "R58") (pin "2") (pinfunction "2_2") (pintype "input"))
    )
    (net (code "40") (name "Net-(L5-TCT)") (class "Default")
      (node (ref "C60") (pin "2") (pinfunction "2_2") (pintype "input"))
      (node (ref "L5") (pin "2") (pinfunction "TCT_2") (pintype "unspecified"))
    )
    (net (code "41") (name "Net-(L5-TXCT)") (class "Default")
      (node (ref "L5") (pin "15") (pinfunction "TXCT_15") (pintype "unspecified"))
      (node (ref "R59") (pin "2") (pinfunction "2_2") (pintype "input"))
    )
    (net (code "42") (name "Net-(R43-Pad1)") (class "Default")
      (node (ref "R43") (pin "1") (pinfunction "1_1") (pintype "input"))
      (node (ref "U11") (pin "4") (pinfunction "4_4") (pintype "unspecified"))
    )
    (net (code "43") (name "Net-(R44-Pad2)") (class "Default")
      (node (ref "R44") (pin "2") (pinfunction "2_2") (pintype "input"))
      (node (ref "U11") (pin "1") (pinfunction "1_1") (pintype "unspecified"))
    )
    (net (code "44") (name "Net-(R51-Pad1)") (class "Default")
      (node (ref "R51") (pin "1") (pinfunction "1_1") (pintype "input"))
      (node (ref "U14") (pin "4") (pinfunction "4_4") (pintype "unspecified"))
    )
    (net (code "45") (name "Net-(R52-Pad2)") (class "Default")
      (node (ref "R52") (pin "2") (pinfunction "2_2") (pintype "input"))
      (node (ref "U14") (pin "1") (pinfunction "1_1") (pintype "unspecified"))
    )
    (net (code "46") (name "Net-(R60-Pad2)") (class "Default")
      (node (ref "R60") (pin "2") (pinfunction "2_2") (pintype "input"))
      (node (ref "RJ1") (pin "4") (pinfunction "4_4") (pintype "unspecified"))
      (node (ref "RJ1") (pin "5") (pinfunction "5_5") (pintype "unspecified"))
    )
    (net (code "47") (name "Net-(R61-Pad2)") (class "Default")
      (node (ref "R61") (pin "2") (pinfunction "2_2") (pintype "input"))
      (node (ref "RJ1") (pin "7") (pinfunction "7_7") (pintype "unspecified"))
      (node (ref "RJ1") (pin "8") (pinfunction "8_8") (pintype "unspecified"))
    )
    (net (code "48") (name "Net-(U2-WPn)") (class "Default")
      (node (ref "R8") (pin "2") (pinfunction "2_2") (pintype "input"))
      (node (ref "U2") (pin "C3") (pinfunction "WPn_C3") (pintype "unspecified"))
    )
    (net (code "49") (name "Net-(U4-EN)") (class "Default")
      (node (ref "R9") (pin "1") (pinfunction "1_1") (pintype "input"))
      (node (ref "U4") (pin "1") (pinfunction "PS/SYNC_1") (pintype "unspecified"))
      (node (ref "U4") (pin "14") (pinfunction "EN_14") (pintype "unspecified"))
    )
    (net (code "50") (name "Net-(U4-FB)") (class "Default")
      (node (ref "R11") (pin "2") (pinfunction "2_2") (pintype "input"))
      (node (ref "R12") (pin "1") (pinfunction "1_1") (pintype "input"))
      (node (ref "U4") (pin "5") (pinfunction "FB_5") (pintype "unspecified"))
    )
    (net (code "51") (name "Net-(U4-L1)") (class "Default")
      (node (ref "L1") (pin "2") (pinfunction "2_2") (pintype "unspecified"))
      (node (ref "U4") (pin "11") (pinfunction "L1_11") (pintype "unspecified"))
    )
    (net (code "52") (name "Net-(U4-L2)") (class "Default")
      (node (ref "L1") (pin "1") (pinfunction "1_1") (pintype "unspecified"))
      (node (ref "U4") (pin "9") (pinfunction "L2_9") (pintype "unspecified"))
    )
    (net (code "53") (name "Net-(U4-PG)") (class "Default")
      (node (ref "R10") (pin "1") (pinfunction "1_1") (pintype "input"))
      (node (ref "U4") (pin "2") (pinfunction "PG_2") (pintype "unspecified"))
    )
    (net (code "54") (name "Net-(U4-Vaux)") (class "Default")
      (node (ref "C26") (pin "1") (pinfunction "1_1") (pintype "input"))
      (node (ref "U4") (pin "3") (pinfunction "Vaux_3") (pintype "unspecified"))
    )
    (net (code "55") (name "Net-(U6-ADJ)") (class "Default")
      (node (ref "R14") (pin "2") (pinfunction "2_2") (pintype "input"))
      (node (ref "R16") (pin "1") (pinfunction "1_1") (pintype "input"))
      (node (ref "U6") (pin "7") (pinfunction "ADJ_7") (pintype "unspecified"))
    )
    (net (code "56") (name "Net-(U6-EN)") (class "Default")
      (node (ref "R13") (pin "2") (pinfunction "2_2") (pintype "input"))
      (node (ref "U6") (pin "2") (pinfunction "EN_2") (pintype "unspecified"))
    )
    (net (code "57") (name "Net-(U9-OUTA)") (class "Default")
      (node (ref "R39") (pin "2") (pinfunction "2_2") (pintype "input"))
      (node (ref "U9") (pin "2") (pinfunction "OUTA_2") (pintype "unspecified"))
    )
    (net (code "58") (name "Net-(U10-DE)") (class "Default")
      (node (ref "U10") (pin "2") (pinfunction "RE#_2") (pintype "unspecified"))
      (node (ref "U10") (pin "3") (pinfunction "DE_3") (pintype "unspecified"))
      (node (ref "U11") (pin "3") (pinfunction "3_3") (pintype "unspecified"))
    )
    (net (code "59") (name "Net-(U10-DI)") (class "Default")
      (node (ref "U10") (pin "4") (pinfunction "DI_4") (pintype "unspecified"))
      (node (ref "U9") (pin "6") (pinfunction "OUTB_6") (pintype "unspecified"))
    )
    (net (code "60") (name "Net-(U10-R0)") (class "Default")
      (node (ref "U10") (pin "1") (pinfunction "R0_1") (pintype "unspecified"))
      (node (ref "U9") (pin "7") (pinfunction "INA_7") (pintype "unspecified"))
    )
    (net (code "61") (name "Net-(U12-INA)") (class "Default")
      (node (ref "U12") (pin "7") (pinfunction "INA_7") (pintype "unspecified"))
      (node (ref "U13") (pin "1") (pinfunction "R0_1") (pintype "unspecified"))
    )
    (net (code "62") (name "Net-(U12-OUTA)") (class "Default")
      (node (ref "R47") (pin "2") (pinfunction "2_2") (pintype "input"))
      (node (ref "U12") (pin "2") (pinfunction "OUTA_2") (pintype "unspecified"))
    )
    (net (code "63") (name "Net-(U12-OUTB)") (class "Default")
      (node (ref "U12") (pin "6") (pinfunction "OUTB_6") (pintype "unspecified"))
      (node (ref "U13") (pin "4") (pinfunction "DI_4") (pintype "unspecified"))
    )
    (net (code "64") (name "Net-(U13-DE)") (class "Default")
      (node (ref "U13") (pin "2") (pinfunction "RE#_2") (pintype "unspecified"))
      (node (ref "U13") (pin "3") (pinfunction "DE_3") (pintype "unspecified"))
      (node (ref "U14") (pin "3") (pinfunction "3_3") (pintype "unspecified"))
    )
    (net (code "65") (name "Net-(U15-AVDD33)") (class "Default")
      (node (ref "C57") (pin "2") (pinfunction "2_2") (pintype "input"))
      (node (ref "L4") (pin "2") (pinfunction "2_2") (pintype "unspecified"))
      (node (ref "U15") (pin "7") (pinfunction "AVDD33_7") (pintype "unspecified"))
    )
    (net (code "66") (name "Net-(U15-AVDDLREG)") (class "Default")
      (node (ref "C54") (pin "1") (pinfunction "1_1") (pintype "input"))
      (node (ref "U15") (pin "2") (pinfunction "AVDDLREG_2") (pintype "unspecified"))
    )
    (net (code "67") (name "Net-(U15-DVDDL_REG)") (class "Default")
      (node (ref "C56") (pin "2") (pinfunction "2_2") (pintype "input"))
      (node (ref "U15") (pin "29") (pinfunction "DVDDL_REG_29") (pintype "unspecified"))
    )
    (net (code "68") (name "Net-(U15-RBIAS)") (class "Default")
      (node (ref "R53") (pin "2") (pinfunction "2_2") (pintype "input"))
      (node (ref "U15") (pin "1") (pinfunction "RBIAS_1") (pintype "unspecified"))
    )
    (net (code "69") (name "Net-(U17B-BYPASS_REG)") (class "Default")
      (node (ref "R1") (pin "2") (pinfunction "2_2") (pintype "input"))
      (node (ref "U17") (pin "48") (pinfunction "BYPASS_REG_48") (pintype "unspecified"))
    )
    (net (code "70") (name "Net-(U17B-VCAP_1)") (class "Default")
      (node (ref "C5") (pin "2") (pinfunction "2_2") (pintype "input"))
      (node (ref "U17") (pin "81") (pinfunction "VCAP_1_81") (pintype "unspecified"))
    )
    (net (code "71") (name "Net-(U17B-VCAP_2)") (class "Default")
      (node (ref "C4") (pin "2") (pinfunction "2_2") (pintype "input"))
      (node (ref "U17") (pin "125") (pinfunction "VCAP_2_125") (pintype "unspecified"))
    )
    (net (code "72") (name "Net-(U17C-VDDA)") (class "Default")
      (node (ref "C2") (pin "2") (pinfunction "2_2") (pintype "input"))
      (node (ref "C3") (pin "2") (pinfunction "2_2") (pintype "input"))
      (node (ref "R2") (pin "1") (pinfunction "1_1") (pintype "input"))
      (node (ref "U17") (pin "39") (pinfunction "VDDA_39") (pintype "unspecified"))
    )
    (net (code "73") (name "Net-(U17C-VREF+)") (class "Default")
      (node (ref "C1") (pin "2") (pinfunction "2_2") (pintype "input"))
      (node (ref "U17") (pin "38") (pinfunction "VREF+_38") (pintype "unspecified"))
    )
    (net (code "74") (name "OSC_IN") (class "Default")
      (node (ref "C17") (pin "1") (pinfunction "1_1") (pintype "input"))
      (node (ref "U1") (pin "3") (pinfunction "OSC2_3") (pintype "unspecified"))
      (node (ref "U17") (pin "29") (pinfunction "PH0-OSC_IN(PH0)_29") (pintype "bidirectional"))
    )
    (net (code "75") (name "OSC_OUT") (class "Default")
      (node (ref "C18") (pin "1") (pinfunction "1_1") (pintype "input"))
      (node (ref "U1") (pin "1") (pinfunction "OSC1_1") (pintype "unspecified"))
      (node (ref "U17") (pin "30") (pinfunction "PH1-OSC_OUT(PH1)_30") (pintype "bidirectional"))
    )
    (net (code "76") (name "PB1_RTS") (class "Default")
      (node (ref "U11") (pin "2") (pinfunction "2_2") (pintype "unspecified"))
    )
    (net (code "77") (name "PB1_RXD") (class "Default")
      (node (ref "R39") (pin "1") (pinfunction "1_1") (pintype "input"))
    )
    (net (code "78") (name "PB1_TXD") (class "Default")
      (node (ref "U9") (pin "3") (pinfunction "INB_3") (pintype "unspecified"))
    )
    (net (code "79") (name "PB2_RTS") (class "Default")
      (node (ref "U14") (pin "2") (pinfunction "2_2") (pintype "unspecified"))
    )
    (net (code "80") (name "PB2_RXD") (class "Default")
      (node (ref "R47") (pin "1") (pinfunction "1_1") (pintype "input"))
    )
    (net (code "81") (name "PB2_TXD") (class "Default")
      (node (ref "U12") (pin "3") (pinfunction "INB_3") (pintype "unspecified"))
    )
    (net (code "82") (name "PBUS1_A") (class "Default")
      (node (ref "CON1") (pin "8") (pinfunction "8_8") (pintype "input"))
      (node (ref "R40") (pin "1") (pinfunction "1_1") (pintype "input"))
      (node (ref "R41") (pin "2") (pinfunction "2_2") (pintype "input"))
      (node (ref "U10") (pin "6") (pinfunction "A_6") (pintype "unspecified"))
    )
    (net (code "83") (name "PBUS1_B") (class "Default")
      (node (ref "CON1") (pin "3") (pinfunction "3_3") (pintype "input"))
      (node (ref "R38") (pin "1") (pinfunction "1_1") (pintype "input"))
      (node (ref "R40") (pin "2") (pinfunction "2_2") (pintype "input"))
      (node (ref "U10") (pin "7") (pinfunction "B_7") (pintype "unspecified"))
    )
    (net (code "84") (name "PBUS2_A") (class "Default")
      (node (ref "CON2") (pin "8") (pinfunction "8_8") (pintype "input"))
      (node (ref "R48") (pin "1") (pinfunction "1_1") (pintype "input"))
      (node (ref "R49") (pin "2") (pinfunction "2_2") (pintype "input"))
      (node (ref "U13") (pin "6") (pinfunction "A_6") (pintype "unspecified"))
    )
    (net (code "85") (name "PBUS2_B") (class "Default")
      (node (ref "CON2") (pin "3") (pinfunction "3_3") (pintype "input"))
      (node (ref "R46") (pin "1") (pinfunction "1_1") (pintype "input"))
      (node (ref "R48") (pin "2") (pinfunction "2_2") (pintype "input"))
      (node (ref "U13") (pin "7") (pinfunction "B_7") (pintype "unspecified"))
    )
    (net (code "86") (name "PF_AB0") (class "Default")
      (node (ref "U17") (pin "16") (pinfunction "PF0_16") (pintype "unspecified"))
    )
    (net (code "87") (name "PF_AB1") (class "Default")
      (node (ref "U17") (pin "17") (pinfunction "PF1_17") (pintype "unspecified"))
    )
    (net (code "88") (name "PF_AB2") (class "Default")
      (node (ref "U17") (pin "18") (pinfunction "PF2_18") (pintype "unspecified"))
    )
    (net (code "89") (name "PF_AB3") (class "Default")
      (node (ref "U17") (pin "19") (pinfunction "PF3_19") (pintype "unspecified"))
    )
    (net (code "90") (name "PF_AB4") (class "Default")
      (node (ref "U17") (pin "20") (pinfunction "PF4_20") (pintype "unspecified"))
    )
    (net (code "91") (name "PF_AB5") (class "Default")
      (node (ref "U17") (pin "21") (pinfunction "PF5_21") (pintype "unspecified"))
    )
    (net (code "92") (name "PF_AB6") (class "Default")
      (node (ref "U17") (pin "24") (pinfunction "PF6_24") (pintype "unspecified"))
    )
    (net (code "93") (name "PF_AB7") (class "Default")
      (node (ref "U17") (pin "25") (pinfunction "PF7_25") (pintype "unspecified"))
    )
    (net (code "94") (name "PF_AB8") (class "Default")
      (node (ref "U17") (pin "26") (pinfunction "PF8_26") (pintype "unspecified"))
    )
    (net (code "95") (name "PF_AB9") (class "Default")
      (node (ref "U17") (pin "27") (pinfunction "PF9_27") (pintype "unspecified"))
    )
    (net (code "96") (name "PF_AB10") (class "Default")
      (node (ref "U17") (pin "28") (pinfunction "PF10_28") (pintype "unspecified"))
    )
    (net (code "97") (name "PF_DB0") (class "Default")
      (node (ref "U17") (pin "117") (pinfunction "PC8_117") (pintype "unspecified"))
    )
    (net (code "98") (name "PF_DB1") (class "Default")
      (node (ref "U17") (pin "118") (pinfunction "PC9_118") (pintype "unspecified"))
    )
    (net (code "99") (name "PF_DB2") (class "Default")
      (node (ref "U17") (pin "139") (pinfunction "PC10_139") (pintype "unspecified"))
    )
    (net (code "100") (name "PF_DB3") (class "Default")
      (node (ref "U17") (pin "140") (pinfunction "PC11_140") (pintype "unspecified"))
    )
    (net (code "101") (name "PF_DB4") (class "Default")
      (node (ref "U17") (pin "141") (pinfunction "PC12_141") (pintype "unspecified"))
    )
    (net (code "102") (name "PF_DB5") (class "Default")
      (node (ref "U17") (pin "8") (pinfunction "PC13_8") (pintype "unspecified"))
    )
    (net (code "103") (name "PF_DB6") (class "Default")
      (node (ref "U17") (pin "9") (pinfunction "PC14-OSC32_IN(PC14)_9") (pintype "bidirectional"))
    )
    (net (code "104") (name "PF_DB7") (class "Default")
      (node (ref "U17") (pin "10") (pinfunction "PC15-OSC32_OUT(PC15)_10") (pintype "bidirectional"))
    )
    (net (code "105") (name "PF_NCS1") (class "Default")
      (node (ref "U17") (pin "176") (pinfunction "PI7_176") (pintype "unspecified"))
    )
    (net (code "106") (name "PF_NCS2") (class "Default")
      (node (ref "U17") (pin "2") (pinfunction "PE3_2") (pintype "unspecified"))
    )
    (net (code "107") (name "PF_NRD") (class "Default")
      (node (ref "U17") (pin "174") (pinfunction "PI5_174") (pintype "unspecified"))
    )
    (net (code "108") (name "PF_NREADY1") (class "Default")
      (node (ref "U17") (pin "173") (pinfunction "PI4_173") (pintype "unspecified"))
    )
    (net (code "109") (name "PF_NREADY2") (class "Default")
      (node (ref "U17") (pin "1") (pinfunction "PE2_1") (pintype "unspecified"))
    )
    (net (code "110") (name "PF_NWR") (class "Default")
      (node (ref "U17") (pin "175") (pinfunction "PI6_175") (pintype "unspecified"))
    )
    (net (code "111") (name "RESET") (class "Default")
      (node (ref "C16") (pin "2") (pinfunction "2_2") (pintype "input"))
      (node (ref "H2") (pin "5") (pinfunction "5_5") (pintype "unspecified"))
      (node (ref "R3") (pin "1") (pinfunction "1_1") (pintype "input"))
      (node (ref "SW1") (pin "1") (pinfunction "1_1") (pintype "input"))
      (node (ref "U17") (pin "31") (pinfunction "NRST_31") (pintype "unspecified"))
    )
    (net (code "112") (name "RMII_CRS_DV") (class "Default")
      (node (ref "U15") (pin "26") (pinfunction "CRS/CRS_DV_26") (pintype "unspecified"))
      (node (ref "U17") (pin "53") (pinfunction "PA7_53") (pintype "unspecified"))
    )
    (net (code "113") (name "RMII_RXD0") (class "Default")
      (node (ref "U15") (pin "9") (pinfunction "RXD[0]_9") (pintype "unspecified"))
      (node (ref "U17") (pin "54") (pinfunction "PC4_54") (pintype "unspecified"))
    )
    (net (code "114") (name "RMII_RXD1") (class "Default")
      (node (ref "U15") (pin "10") (pinfunction "RXD[1]_10") (pintype "unspecified"))
      (node (ref "U17") (pin "55") (pinfunction "PC5_55") (pintype "unspecified"))
    )
    (net (code "115") (name "RMII_TXD0") (class "Default")
      (node (ref "U15") (pin "16") (pinfunction "TXD[0]_16") (pintype "unspecified"))
      (node (ref "U17") (pin "156") (pinfunction "PG13_156") (pintype "unspecified"))
    )
    (net (code "116") (name "RMII_TXD1") (class "Default")
      (node (ref "U15") (pin "17") (pinfunction "TXD[1]_17") (pintype "unspecified"))
      (node (ref "U17") (pin "157") (pinfunction "PG14_157") (pintype "unspecified"))
    )
    (net (code "117") (name "RMII_TX_EN") (class "Default")
      (node (ref "U15") (pin "20") (pinfunction "TX_EN_20") (pintype "unspecified"))
      (node (ref "U17") (pin "80") (pinfunction "PB11_80") (pintype "unspecified"))
    )
    (net (code "118") (name "RX_N") (class "Default")
      (node (ref "L5") (pin "9") (pinfunction "RX-_9") (pintype "unspecified"))
      (node (ref "RJ1") (pin "6") (pinfunction "6_6") (pintype "unspecified"))
    )
    (net (code "119") (name "RX_P") (class "Default")
      (node (ref "L5") (pin "11") (pinfunction "RX+_11") (pintype "unspecified"))
      (node (ref "RJ1") (pin "3") (pinfunction "3_3") (pintype "unspecified"))
    )
    (net (code "120") (name "SWCLK") (class "Default")
      (node (ref "H2") (pin "2") (pinfunction "2_2") (pintype "unspecified"))
      (node (ref "U17") (pin "137") (pinfunction "PA14(JTCK-SWCLK)_137") (pintype "unspecified"))
    )
    (net (code "121") (name "SWDIO") (class "Default")
      (node (ref "H2") (pin "3") (pinfunction "3_3") (pintype "unspecified"))
      (node (ref "U17") (pin "124") (pinfunction "PA13(JTMS-SWDIO)_124") (pintype "unspecified"))
    )
    (net (code "122") (name "TX_N") (class "Default")
      (node (ref "L5") (pin "14") (pinfunction "TX-_14") (pintype "unspecified"))
      (node (ref "RJ1") (pin "2") (pinfunction "2_2") (pintype "unspecified"))
    )
    (net (code "123") (name "TX_P") (class "Default")
      (node (ref "L5") (pin "16") (pinfunction "TX+_16") (pintype "unspecified"))
      (node (ref "RJ1") (pin "1") (pinfunction "1_1") (pintype "unspecified"))
    )
    (net (code "124") (name "VCC33V") (class "Default")
      (node (ref "C10") (pin "2") (pinfunction "2_2") (pintype "input"))
      (node (ref "C11") (pin "2") (pinfunction "2_2") (pintype "input"))
      (node (ref "C12") (pin "2") (pinfunction "2_2") (pintype "input"))
      (node (ref "C13") (pin "2") (pinfunction "2_2") (pintype "input"))
      (node (ref "C14") (pin "2") (pinfunction "2_2") (pintype "input"))
      (node (ref "C15") (pin "2") (pinfunction "2_2") (pintype "input"))
      (node (ref "C19") (pin "2") (pinfunction "2_2") (pintype "input"))
      (node (ref "C20") (pin "2") (pinfunction "2_2") (pintype "input"))
      (node (ref "C21") (pin "2") (pinfunction "2_2") (pintype "input"))
      (node (ref "C22") (pin "2") (pinfunction "2_2") (pintype "input"))
      (node (ref "C23") (pin "2") (pinfunction "2_2") (pintype "input"))
      (node (ref "C24") (pin "2") (pinfunction "2_2") (pintype "input"))
      (node (ref "C33") (pin "2") (pinfunction "2_2") (pintype "input"))
      (node (ref "C34") (pin "2") (pinfunction "2_2") (pintype "input"))
      (node (ref "C6") (pin "2") (pinfunction "2_2") (pintype "input"))
      (node (ref "C7") (pin "2") (pinfunction "2_2") (pintype "input"))
      (node (ref "C8") (pin "2") (pinfunction "2_2") (pintype "input"))
      (node (ref "C9") (pin "2") (pinfunction "2_2") (pintype "input"))
      (node (ref "H1") (pin "1") (pinfunction "1_1") (pintype "input"))
      (node (ref "H1") (pin "2") (pinfunction "2_2") (pintype "input"))
      (node (ref "H2") (pin "4") (pinfunction "4_4") (pintype "unspecified"))
      (node (ref "L4") (pin "1") (pinfunction "1_1") (pintype "unspecified"))
      (node (ref "R14") (pin "1") (pinfunction "1_1") (pintype "input"))
      (node (ref "R2") (pin "2") (pinfunction "2_2") (pintype "input"))
      (node (ref "R3") (pin "2") (pinfunction "2_2") (pintype "input"))
      (node (ref "R44") (pin "1") (pinfunction "1_1") (pintype "input"))
      (node (ref "R52") (pin "1") (pinfunction "1_1") (pintype "input"))
      (node (ref "R6") (pin "2") (pinfunction "2_2") (pintype "input"))
      (node (ref "R7") (pin "2") (pinfunction "2_2") (pintype "input"))
      (node (ref "R8") (pin "1") (pinfunction "1_1") (pintype "input"))
      (node (ref "U12") (pin "1") (pinfunction "VCC1_1") (pintype "unspecified"))
      (node (ref "U15") (pin "14") (pinfunction "DVDD33_14") (pintype "unspecified"))
      (node (ref "U17") (pin "103") (pinfunction "VDD_103") (pintype "unspecified"))
      (node (ref "U17") (pin "114") (pinfunction "VDD_114") (pintype "unspecified"))
      (node (ref "U17") (pin "127") (pinfunction "VDD_127") (pintype "unspecified"))
      (node (ref "U17") (pin "136") (pinfunction "VDD_136") (pintype "unspecified"))
      (node (ref "U17") (pin "149") (pinfunction "VDD_149") (pintype "unspecified"))
      (node (ref "U17") (pin "15") (pinfunction "VDD_15") (pintype "unspecified"))
      (node (ref "U17") (pin "159") (pinfunction "VDD_159") (pintype "unspecified"))
      (node (ref "U17") (pin "171") (pinfunction "PDR_ON_171") (pintype "unspecified"))
      (node (ref "U17") (pin "172") (pinfunction "VDD_172") (pintype "unspecified"))
      (node (ref "U17") (pin "23") (pinfunction "VDD_23") (pintype "unspecified"))
      (node (ref "U17") (pin "36") (pinfunction "VDD_36") (pintype "unspecified"))
      (node (ref "U17") (pin "49") (pinfunction "VDD_49") (pintype "unspecified"))
      (node (ref "U17") (pin "62") (pinfunction "VDD_62") (pintype "unspecified"))
      (node (ref "U17") (pin "72") (pinfunction "VDD_72") (pintype "unspecified"))
      (node (ref "U17") (pin "82") (pinfunction "VDD_82") (pintype "unspecified"))
      (node (ref "U17") (pin "91") (pinfunction "VDD_91") (pintype "unspecified"))
      (node (ref "U2") (pin "D3") (pinfunction "VCC2_D3") (pintype "unspecified"))
      (node (ref "U2") (pin "G4") (pinfunction "VCC2_G4") (pintype "unspecified"))
      (node (ref "U2") (pin "H8") (pinfunction "VCC_H8") (pintype "unspecified"))
      (node (ref "U2") (pin "J6") (pinfunction "VCC_J6") (pintype "unspecified"))
      (node (ref "U3") (pin "8") (pinfunction "VCC_8") (pintype "unspecified"))
      (node (ref "U6") (pin "6") (pinfunction "VOUT_6") (pintype "unspecified"))
      (node (ref "U9") (pin "1") (pinfunction "VCC1_1") (pintype "unspecified"))
    )
    (net (code "125") (name "VDD50V") (class "Default")
      (node (ref "C29") (pin "2") (pinfunction "2_2") (pintype "input"))
      (node (ref "C30") (pin "1") (pinfunction "1_1") (pintype "input"))
      (node (ref "C31") (pin "1") (pinfunction "1_1") (pintype "input"))
      (node (ref "C32") (pin "1") (pinfunction "1_1") (pintype "input"))
      (node (ref "C35") (pin "2") (pinfunction "2_2") (pintype "input"))
      (node (ref "R10") (pin "2") (pinfunction "2_2") (pintype "input"))
      (node (ref "R11") (pin "1") (pinfunction "1_1") (pintype "input"))
      (node (ref "R13") (pin "1") (pinfunction "1_1") (pintype "input"))
      (node (ref "U4") (pin "7") (pinfunction "Vout_7") (pintype "unspecified"))
      (node (ref "U4") (pin "8") (pinfunction "Vout_8") (pintype "unspecified"))
      (node (ref "U5") (pin "1") (pinfunction "+VIN_1") (pintype "unspecified"))
      (node (ref "U6") (pin "3") (pinfunction "VIN_3") (pintype "unspecified"))
    )
    (net (code "126") (name "VIN12V") (class "Default")
      (node (ref "C25") (pin "1") (pinfunction "1_1") (pintype "input"))
      (node (ref "C27") (pin "2") (pinfunction "2_2") (pintype "input"))
      (node (ref "C28") (pin "2") (pinfunction "2_2") (pintype "input"))
      (node (ref "DC1") (pin "1") (pinfunction "4_1") (pintype "input"))
      (node (ref "R9") (pin "2") (pinfunction "2_2") (pintype "input"))
      (node (ref "U4") (pin "12") (pinfunction "Vin_12") (pintype "unspecified"))
      (node (ref "U4") (pin "13") (pinfunction "Vin_13") (pintype "unspecified"))
    )
    (net (code "127") (name "XGND") (class "Default")
      (node (ref "C36") (pin "1") (pinfunction "1_1") (pintype "input"))
      (node (ref "C37") (pin "1") (pinfunction "1_1") (pintype "input"))
      (node (ref "C50") (pin "1") (pinfunction "1_1") (pintype "input"))
      (node (ref "C51") (pin "1") (pinfunction "1_1") (pintype "input"))
      (node (ref "C52") (pin "1") (pinfunction "1_1") (pintype "input"))
      (node (ref "C53") (pin "1") (pinfunction "1_1") (pintype "input"))
      (node (ref "R15") (pin "1") (pinfunction "1_1") (pintype "input"))
      (node (ref "R41") (pin "1") (pinfunction "1_1") (pintype "input"))
      (node (ref "R42") (pin "1") (pinfunction "1_1") (pintype "input"))
      (node (ref "R49") (pin "1") (pinfunction "1_1") (pintype "input"))
      (node (ref "R50") (pin "1") (pinfunction "1_1") (pintype "input"))
      (node (ref "U10") (pin "5") (pinfunction "VO1_5") (pintype "unspecified"))
      (node (ref "U12") (pin "5") (pinfunction "GND2_5") (pintype "unspecified"))
      (node (ref "U13") (pin "5") (pinfunction "VO1_5") (pintype "unspecified"))
      (node (ref "U5") (pin "5") (pinfunction "-VOUT_5") (pintype "unspecified"))
      (node (ref "U9") (pin "5") (pinfunction "GND2_5") (pintype "unspecified"))
    )
    (net (code "128") (name "XVDD50V") (class "Default")
      (node (ref "C36") (pin "2") (pinfunction "2_2") (pintype "input"))
      (node (ref "C37") (pin "2") (pinfunction "2_2") (pintype "input"))
      (node (ref "C50") (pin "2") (pinfunction "2_2") (pintype "input"))
      (node (ref "C51") (pin "2") (pinfunction "2_2") (pintype "input"))
      (node (ref "C52") (pin "2") (pinfunction "2_2") (pintype "input"))
      (node (ref "C53") (pin "2") (pinfunction "2_2") (pintype "input"))
      (node (ref "R15") (pin "2") (pinfunction "2_2") (pintype "input"))
      (node (ref "R37") (pin "1") (pinfunction "1_1") (pintype "input"))
      (node (ref "R38") (pin "2") (pinfunction "2_2") (pintype "input"))
      (node (ref "R43") (pin "2") (pinfunction "2_2") (pintype "input"))
      (node (ref "R45") (pin "1") (pinfunction "1_1") (pintype "input"))
      (node (ref "R46") (pin "2") (pinfunction "2_2") (pintype "input"))
      (node (ref "R51") (pin "2") (pinfunction "2_2") (pintype "input"))
      (node (ref "U10") (pin "8") (pinfunction "VCC_8") (pintype "unspecified"))
      (node (ref "U12") (pin "8") (pinfunction "VCC2_8") (pintype "unspecified"))
      (node (ref "U13") (pin "8") (pinfunction "VCC_8") (pintype "unspecified"))
      (node (ref "U5") (pin "7") (pinfunction "+VOUT_7") (pintype "unspecified"))
      (node (ref "U9") (pin "8") (pinfunction "VCC2_8") (pintype "unspecified"))
    )
    (net (code "129") (name "unconnected-(C38-Pad1)") (class "Default")
      (node (ref "C38") (pin "1") (pinfunction "1_1") (pintype "input"))
    )
    (net (code "130") (name "unconnected-(C38-Pad2)") (class "Default")
      (node (ref "C38") (pin "2") (pinfunction "2_2") (pintype "input"))
    )
    (net (code "131") (name "unconnected-(C39-Pad1)") (class "Default")
      (node (ref "C39") (pin "1") (pinfunction "1_1") (pintype "input"))
    )
    (net (code "132") (name "unconnected-(C39-Pad2)") (class "Default")
      (node (ref "C39") (pin "2") (pinfunction "2_2") (pintype "input"))
    )
    (net (code "133") (name "unconnected-(C40-Pad1)") (class "Default")
      (node (ref "C40") (pin "1") (pinfunction "1_1") (pintype "input"))
    )
    (net (code "134") (name "unconnected-(C40-Pad2)") (class "Default")
      (node (ref "C40") (pin "2") (pinfunction "2_2") (pintype "input"))
    )
    (net (code "135") (name "unconnected-(C41-Pad1)") (class "Default")
      (node (ref "C41") (pin "1") (pinfunction "1_1") (pintype "input"))
    )
    (net (code "136") (name "unconnected-(C41-Pad2)") (class "Default")
      (node (ref "C41") (pin "2") (pinfunction "2_2") (pintype "input"))
    )
    (net (code "137") (name "unconnected-(C42-Pad1)") (class "Default")
      (node (ref "C42") (pin "1") (pinfunction "1_1") (pintype "input"))
    )
    (net (code "138") (name "unconnected-(C42-Pad2)") (class "Default")
      (node (ref "C42") (pin "2") (pinfunction "2_2") (pintype "input"))
    )
    (net (code "139") (name "unconnected-(C43-Pad1)") (class "Default")
      (node (ref "C43") (pin "1") (pinfunction "1_1") (pintype "input"))
    )
    (net (code "140") (name "unconnected-(C43-Pad2)") (class "Default")
      (node (ref "C43") (pin "2") (pinfunction "2_2") (pintype "input"))
    )
    (net (code "141") (name "unconnected-(CON1-Pad1)") (class "Default")
      (node (ref "CON1") (pin "1") (pinfunction "1_1") (pintype "input+no_connect"))
    )
    (net (code "142") (name "unconnected-(CON1-Pad2)") (class "Default")
      (node (ref "CON1") (pin "2") (pinfunction "2_2") (pintype "input+no_connect"))
    )
    (net (code "143") (name "unconnected-(CON1-Pad4)") (class "Default")
      (node (ref "CON1") (pin "4") (pinfunction "4_4") (pintype "input+no_connect"))
    )
    (net (code "144") (name "unconnected-(CON1-Pad7)") (class "Default")
      (node (ref "CON1") (pin "7") (pinfunction "7_7") (pintype "input+no_connect"))
    )
    (net (code "145") (name "unconnected-(CON1-Pad9)") (class "Default")
      (node (ref "CON1") (pin "9") (pinfunction "9_9") (pintype "input+no_connect"))
    )
    (net (code "146") (name "unconnected-(CON2-Pad1)") (class "Default")
      (node (ref "CON2") (pin "1") (pinfunction "1_1") (pintype "input+no_connect"))
    )
    (net (code "147") (name "unconnected-(CON2-Pad2)") (class "Default")
      (node (ref "CON2") (pin "2") (pinfunction "2_2") (pintype "input+no_connect"))
    )
    (net (code "148") (name "unconnected-(CON2-Pad4)") (class "Default")
      (node (ref "CON2") (pin "4") (pinfunction "4_4") (pintype "input+no_connect"))
    )
    (net (code "149") (name "unconnected-(CON2-Pad7)") (class "Default")
      (node (ref "CON2") (pin "7") (pinfunction "7_7") (pintype "input+no_connect"))
    )
    (net (code "150") (name "unconnected-(CON2-Pad9)") (class "Default")
      (node (ref "CON2") (pin "9") (pinfunction "9_9") (pintype "input+no_connect"))
    )
    (net (code "151") (name "unconnected-(L2-Pad1)") (class "Default")
      (node (ref "L2") (pin "1") (pinfunction "1_1") (pintype "unspecified"))
    )
    (net (code "152") (name "unconnected-(L2-Pad2)") (class "Default")
      (node (ref "L2") (pin "2") (pinfunction "2_2") (pintype "unspecified"))
    )
    (net (code "153") (name "unconnected-(L5-Pad4)") (class "Default")
      (node (ref "L5") (pin "4") (pinfunction "4_4") (pintype "unspecified+no_connect"))
    )
    (net (code "154") (name "unconnected-(L5-Pad5)") (class "Default")
      (node (ref "L5") (pin "5") (pinfunction "5_5") (pintype "unspecified+no_connect"))
    )
    (net (code "155") (name "unconnected-(L5-Pad12)") (class "Default")
      (node (ref "L5") (pin "12") (pinfunction "12_12") (pintype "unspecified+no_connect"))
    )
    (net (code "156") (name "unconnected-(L5-Pad13)") (class "Default")
      (node (ref "L5") (pin "13") (pinfunction "13_13") (pintype "unspecified+no_connect"))
    )
    (net (code "157") (name "unconnected-(MARK1-Pad1)") (class "Default")
      (node (ref "MARK1") (pin "1") (pinfunction "1_1") (pintype "input"))
    )
    (net (code "158") (name "unconnected-(MARK2-Pad1)") (class "Default")
      (node (ref "MARK2") (pin "1") (pinfunction "1_1") (pintype "input"))
    )
    (net (code "159") (name "unconnected-(MARK3-Pad1)") (class "Default")
      (node (ref "MARK3") (pin "1") (pinfunction "1_1") (pintype "input"))
    )
    (net (code "160") (name "unconnected-(MARK4-Pad1)") (class "Default")
      (node (ref "MARK4") (pin "1") (pinfunction "1_1") (pintype "input"))
    )
    (net (code "161") (name "unconnected-(MARK5-Pad1)") (class "Default")
      (node (ref "MARK5") (pin "1") (pinfunction "1_1") (pintype "input"))
    )
    (net (code "162") (name "unconnected-(MARK6-Pad1)") (class "Default")
      (node (ref "MARK6") (pin "1") (pinfunction "1_1") (pintype "input"))
    )
    (net (code "163") (name "unconnected-(MARK7-Pad1)") (class "Default")
      (node (ref "MARK7") (pin "1") (pinfunction "1_1") (pintype "input"))
    )
    (net (code "164") (name "unconnected-(MARK8-Pad1)") (class "Default")
      (node (ref "MARK8") (pin "1") (pinfunction "1_1") (pintype "input"))
    )
    (net (code "165") (name "unconnected-(OSC1-EOH-Pad1)") (class "Default")
      (node (ref "OSC1") (pin "1") (pinfunction "EOH_1") (pintype "unspecified"))
    )
    (net (code "166") (name "unconnected-(OSC1-GND-Pad2)") (class "Default")
      (node (ref "OSC1") (pin "2") (pinfunction "GND_2") (pintype "unspecified"))
    )
    (net (code "167") (name "unconnected-(OSC1-Output-Pad3)") (class "Default")
      (node (ref "OSC1") (pin "3") (pinfunction "Output_3") (pintype "unspecified"))
    )
    (net (code "168") (name "unconnected-(OSC1-VCC-Pad4)") (class "Default")
      (node (ref "OSC1") (pin "4") (pinfunction "VCC_4") (pintype "unspecified"))
    )
    (net (code "169") (name "unconnected-(R17-Pad1)") (class "Default")
      (node (ref "R17") (pin "1") (pinfunction "1_1") (pintype "input"))
    )
    (net (code "170") (name "unconnected-(R17-Pad2)") (class "Default")
      (node (ref "R17") (pin "2") (pinfunction "2_2") (pintype "input"))
    )
    (net (code "171") (name "unconnected-(R18-Pad1)") (class "Default")
      (node (ref "R18") (pin "1") (pinfunction "1_1") (pintype "input"))
    )
    (net (code "172") (name "unconnected-(R18-Pad2)") (class "Default")
      (node (ref "R18") (pin "2") (pinfunction "2_2") (pintype "input"))
    )
    (net (code "173") (name "unconnected-(R19-Pad1)") (class "Default")
      (node (ref "R19") (pin "1") (pinfunction "1_1") (pintype "input"))
    )
    (net (code "174") (name "unconnected-(R19-Pad2)") (class "Default")
      (node (ref "R19") (pin "2") (pinfunction "2_2") (pintype "input"))
    )
    (net (code "175") (name "unconnected-(R20-Pad1)") (class "Default")
      (node (ref "R20") (pin "1") (pinfunction "1_1") (pintype "input"))
    )
    (net (code "176") (name "unconnected-(R20-Pad2)") (class "Default")
      (node (ref "R20") (pin "2") (pinfunction "2_2") (pintype "input"))
    )
    (net (code "177") (name "unconnected-(R21-Pad1)") (class "Default")
      (node (ref "R21") (pin "1") (pinfunction "1_1") (pintype "input"))
    )
    (net (code "178") (name "unconnected-(R21-Pad2)") (class "Default")
      (node (ref "R21") (pin "2") (pinfunction "2_2") (pintype "input"))
    )
    (net (code "179") (name "unconnected-(R22-Pad1)") (class "Default")
      (node (ref "R22") (pin "1") (pinfunction "1_1") (pintype "input"))
    )
    (net (code "180") (name "unconnected-(R22-Pad2)") (class "Default")
      (node (ref "R22") (pin "2") (pinfunction "2_2") (pintype "input"))
    )
    (net (code "181") (name "unconnected-(R23-Pad1)") (class "Default")
      (node (ref "R23") (pin "1") (pinfunction "1_1") (pintype "input"))
    )
    (net (code "182") (name "unconnected-(R23-Pad2)") (class "Default")
      (node (ref "R23") (pin "2") (pinfunction "2_2") (pintype "input"))
    )
    (net (code "183") (name "unconnected-(R24-Pad1)") (class "Default")
      (node (ref "R24") (pin "1") (pinfunction "1_1") (pintype "input"))
    )
    (net (code "184") (name "unconnected-(R24-Pad2)") (class "Default")
      (node (ref "R24") (pin "2") (pinfunction "2_2") (pintype "input"))
    )
    (net (code "185") (name "unconnected-(R25-Pad1)") (class "Default")
      (node (ref "R25") (pin "1") (pinfunction "1_1") (pintype "input"))
    )
    (net (code "186") (name "unconnected-(R25-Pad2)") (class "Default")
      (node (ref "R25") (pin "2") (pinfunction "2_2") (pintype "input"))
    )
    (net (code "187") (name "unconnected-(R26-Pad1)") (class "Default")
      (node (ref "R26") (pin "1") (pinfunction "1_1") (pintype "input"))
    )
    (net (code "188") (name "unconnected-(R26-Pad2)") (class "Default")
      (node (ref "R26") (pin "2") (pinfunction "2_2") (pintype "input"))
    )
    (net (code "189") (name "unconnected-(U1-GND-Pad2)") (class "Default")
      (node (ref "U1") (pin "2") (pinfunction "GND_2") (pintype "unspecified+no_connect"))
    )
    (net (code "190") (name "unconnected-(U1-GND-Pad4)") (class "Default")
      (node (ref "U1") (pin "4") (pinfunction "GND_4") (pintype "unspecified+no_connect"))
    )
    (net (code "191") (name "unconnected-(U2-DNU-PadG3)") (class "Default")
      (node (ref "U2") (pin "G3") (pinfunction "DNU_G3") (pintype "unspecified+no_connect"))
    )
    (net (code "192") (name "unconnected-(U2-DNU-PadG8)") (class "Default")
      (node (ref "U2") (pin "G8") (pinfunction "DNU_G8") (pintype "unspecified+no_connect"))
    )
    (net (code "193") (name "unconnected-(U2-LOCK-PadG5)") (class "Default")
      (node (ref "U2") (pin "G5") (pinfunction "LOCK_G5") (pintype "unspecified+no_connect"))
    )
    (net (code "194") (name "unconnected-(U2-NC-PadA1)") (class "Default")
      (node (ref "U2") (pin "A1") (pinfunction "NC_A1") (pintype "unspecified+no_connect"))
    )
    (net (code "195") (name "unconnected-(U2-NC-PadA2)") (class "Default")
      (node (ref "U2") (pin "A2") (pinfunction "NC_A2") (pintype "unspecified+no_connect"))
    )
    (net (code "196") (name "unconnected-(U2-NC-PadA9)") (class "Default")
      (node (ref "U2") (pin "A9") (pinfunction "NC_A9") (pintype "unspecified+no_connect"))
    )
    (net (code "197") (name "unconnected-(U2-NC-PadA10)") (class "Default")
      (node (ref "U2") (pin "A10") (pinfunction "NC_A10") (pintype "unspecified+no_connect"))
    )
    (net (code "198") (name "unconnected-(U2-NC-PadB1)") (class "Default")
      (node (ref "U2") (pin "B1") (pinfunction "NC_B1") (pintype "unspecified+no_connect"))
    )
    (net (code "199") (name "unconnected-(U2-NC-PadB9)") (class "Default")
      (node (ref "U2") (pin "B9") (pinfunction "NC_B9") (pintype "unspecified+no_connect"))
    )
    (net (code "200") (name "unconnected-(U2-NC-PadB10)") (class "Default")
      (node (ref "U2") (pin "B10") (pinfunction "NC_B10") (pintype "unspecified+no_connect"))
    )
    (net (code "201") (name "unconnected-(U2-NC-PadD6)") (class "Default")
      (node (ref "U2") (pin "D6") (pinfunction "NC_D6") (pintype "unspecified+no_connect"))
    )
    (net (code "202") (name "unconnected-(U2-NC-PadD7)") (class "Default")
      (node (ref "U2") (pin "D7") (pinfunction "NC_D7") (pintype "unspecified+no_connect"))
    )
    (net (code "203") (name "unconnected-(U2-NC-PadD8)") (class "Default")
      (node (ref "U2") (pin "D8") (pinfunction "NC_D8") (pintype "unspecified+no_connect"))
    )
    (net (code "204") (name "unconnected-(U2-NC-PadE3)") (class "Default")
      (node (ref "U2") (pin "E3") (pinfunction "NC_E3") (pintype "unspecified+no_connect"))
    )
    (net (code "205") (name "unconnected-(U2-NC-PadE4)") (class "Default")
      (node (ref "U2") (pin "E4") (pinfunction "NC_E4") (pintype "unspecified+no_connect"))
    )
    (net (code "206") (name "unconnected-(U2-NC-PadE5)") (class "Default")
      (node (ref "U2") (pin "E5") (pinfunction "NC_E5") (pintype "unspecified+no_connect"))
    )
    (net (code "207") (name "unconnected-(U2-NC-PadE6)") (class "Default")
      (node (ref "U2") (pin "E6") (pinfunction "NC_E6") (pintype "unspecified+no_connect"))
    )
    (net (code "208") (name "unconnected-(U2-NC-PadE7)") (class "Default")
      (node (ref "U2") (pin "E7") (pinfunction "NC_E7") (pintype "unspecified+no_connect"))
    )
    (net (code "209") (name "unconnected-(U2-NC-PadE8)") (class "Default")
      (node (ref "U2") (pin "E8") (pinfunction "NC_E8") (pintype "unspecified+no_connect"))
    )
    (net (code "210") (name "unconnected-(U2-NC-PadF3)") (class "Default")
      (node (ref "U2") (pin "F3") (pinfunction "NC_F3") (pintype "unspecified+no_connect"))
    )
    (net (code "211") (name "unconnected-(U2-NC-PadF4)") (class "Default")
      (node (ref "U2") (pin "F4") (pinfunction "NC_F4") (pintype "unspecified+no_connect"))
    )
    (net (code "212") (name "unconnected-(U2-NC-PadF5)") (class "Default")
      (node (ref "U2") (pin "F5") (pinfunction "NC_F5") (pintype "unspecified+no_connect"))
    )
    (net (code "213") (name "unconnected-(U2-NC-PadF6)") (class "Default")
      (node (ref "U2") (pin "F6") (pinfunction "NC_F6") (pintype "unspecified+no_connect"))
    )
    (net (code "214") (name "unconnected-(U2-NC-PadF8)") (class "Default")
      (node (ref "U2") (pin "F8") (pinfunction "NC_F8") (pintype "unspecified+no_connect"))
    )
    (net (code "215") (name "unconnected-(U2-NC-PadG6)") (class "Default")
      (node (ref "U2") (pin "G6") (pinfunction "NC_G6") (pintype "unspecified+no_connect"))
    )
    (net (code "216") (name "unconnected-(U2-NC-PadG7)") (class "Default")
      (node (ref "U2") (pin "G7") (pinfunction "NC_G7") (pintype "unspecified+no_connect"))
    )
    (net (code "217") (name "unconnected-(U2-NC-PadH3)") (class "Default")
      (node (ref "U2") (pin "H3") (pinfunction "NC_H3") (pintype "unspecified+no_connect"))
    )
    (net (code "218") (name "unconnected-(U2-NC-PadH5)") (class "Default")
      (node (ref "U2") (pin "H5") (pinfunction "NC_H5") (pintype "unspecified+no_connect"))
    )
    (net (code "219") (name "unconnected-(U2-NC-PadH6)") (class "Default")
      (node (ref "U2") (pin "H6") (pinfunction "NC_H6") (pintype "unspecified+no_connect"))
    )
    (net (code "220") (name "unconnected-(U2-NC-PadH7)") (class "Default")
      (node (ref "U2") (pin "H7") (pinfunction "NC_H7") (pintype "unspecified+no_connect"))
    )
    (net (code "221") (name "unconnected-(U2-NC-PadJ3)") (class "Default")
      (node (ref "U2") (pin "J3") (pinfunction "NC_J3") (pintype "unspecified+no_connect"))
    )
    (net (code "222") (name "unconnected-(U2-NC-PadJ5)") (class "Default")
      (node (ref "U2") (pin "J5") (pinfunction "NC_J5") (pintype "unspecified+no_connect"))
    )
    (net (code "223") (name "unconnected-(U2-NC-PadL1)") (class "Default")
      (node (ref "U2") (pin "L1") (pinfunction "NC_L1") (pintype "unspecified+no_connect"))
    )
    (net (code "224") (name "unconnected-(U2-NC-PadL2)") (class "Default")
      (node (ref "U2") (pin "L2") (pinfunction "NC_L2") (pintype "unspecified+no_connect"))
    )
    (net (code "225") (name "unconnected-(U2-NC-PadL9)") (class "Default")
      (node (ref "U2") (pin "L9") (pinfunction "NC_L9") (pintype "unspecified+no_connect"))
    )
    (net (code "226") (name "unconnected-(U2-NC-PadL10)") (class "Default")
      (node (ref "U2") (pin "L10") (pinfunction "NC_L10") (pintype "unspecified+no_connect"))
    )
    (net (code "227") (name "unconnected-(U2-NC-PadM1)") (class "Default")
      (node (ref "U2") (pin "M1") (pinfunction "NC_M1") (pintype "unspecified+no_connect"))
    )
    (net (code "228") (name "unconnected-(U2-NC-PadM2)") (class "Default")
      (node (ref "U2") (pin "M2") (pinfunction "NC_M2") (pintype "unspecified+no_connect"))
    )
    (net (code "229") (name "unconnected-(U2-NC-PadM9)") (class "Default")
      (node (ref "U2") (pin "M9") (pinfunction "NC_M9") (pintype "unspecified+no_connect"))
    )
    (net (code "230") (name "unconnected-(U2-NC-PadM10)") (class "Default")
      (node (ref "U2") (pin "M10") (pinfunction "NC_M10") (pintype "unspecified+no_connect"))
    )
    (net (code "231") (name "unconnected-(U6-NC-Pad1)") (class "Default")
      (node (ref "U6") (pin "1") (pinfunction "NC_1") (pintype "unspecified+no_connect"))
    )
    (net (code "232") (name "unconnected-(U6-NC-Pad4)") (class "Default")
      (node (ref "U6") (pin "4") (pinfunction "NC_4") (pintype "unspecified+no_connect"))
    )
    (net (code "233") (name "unconnected-(U6-NC-Pad5)") (class "Default")
      (node (ref "U6") (pin "5") (pinfunction "NC_5") (pintype "unspecified+no_connect"))
    )
    (net (code "234") (name "unconnected-(U15-COL-Pad27)") (class "Default")
      (node (ref "U15") (pin "27") (pinfunction "COL_27") (pintype "unspecified+no_connect"))
    )
    (net (code "235") (name "unconnected-(U15-LED1{slash}PHYADD1-Pad25)") (class "Default")
      (node (ref "U15") (pin "25") (pinfunction "LED1/PHYADD1_25") (pintype "unspecified+no_connect"))
    )
    (net (code "236") (name "unconnected-(U15-LEDO{slash}PHYADDO-Pad24)") (class "Default")
      (node (ref "U15") (pin "24") (pinfunction "LEDO/PHYADDO_24") (pintype "unspecified+no_connect"))
    )
    (net (code "237") (name "unconnected-(U15-NC-Pad30)") (class "Default")
      (node (ref "U15") (pin "30") (pinfunction "NC_30") (pintype "unspecified+no_connect"))
    )
    (net (code "238") (name "unconnected-(U15-RESET_N-Pad21)") (class "Default")
      (node (ref "U15") (pin "21") (pinfunction "RESET_N_21") (pintype "unspecified+no_connect"))
    )
    (net (code "239") (name "unconnected-(U15-RXC-Pad13)") (class "Default")
      (node (ref "U15") (pin "13") (pinfunction "RXC_13") (pintype "unspecified+no_connect"))
    )
    (net (code "240") (name "unconnected-(U15-RXD3{slash}CLK_CTL-Pad12)") (class "Default")
      (node (ref "U15") (pin "12") (pinfunction "RXD3/CLK_CTL_12") (pintype "unspecified+no_connect"))
    )
    (net (code "241") (name "unconnected-(U15-RXD[2]{slash}INT_N-Pad11)") (class "Default")
      (node (ref "U15") (pin "11") (pinfunction "RXD[2]/INT_N_11") (pintype "unspecified+no_connect"))
    )
    (net (code "242") (name "unconnected-(U15-RX_DV-Pad8)") (class "Default")
      (node (ref "U15") (pin "8") (pinfunction "RX_DV_8") (pintype "unspecified+no_connect"))
    )
    (net (code "243") (name "unconnected-(U15-RX_ER-Pad28)") (class "Default")
      (node (ref "U15") (pin "28") (pinfunction "RX_ER_28") (pintype "unspecified+no_connect"))
    )
    (net (code "244") (name "unconnected-(U15-TXC-Pad15)") (class "Default")
      (node (ref "U15") (pin "15") (pinfunction "TXC_15") (pintype "unspecified+no_connect"))
    )
    (net (code "245") (name "unconnected-(U15-TXD[2]-Pad18)") (class "Default")
      (node (ref "U15") (pin "18") (pinfunction "TXD[2]_18") (pintype "unspecified+no_connect"))
    )
    (net (code "246") (name "unconnected-(U15-TXD[3]-Pad19)") (class "Default")
      (node (ref "U15") (pin "19") (pinfunction "TXD[3]_19") (pintype "unspecified+no_connect"))
    )
    (net (code "247") (name "unconnected-(U16-GND-Pad2)") (class "Default")
      (node (ref "U16") (pin "2") (pinfunction "GND_2") (pintype "unspecified+no_connect"))
    )
    (net (code "248") (name "unconnected-(U16-GND-Pad4)") (class "Default")
      (node (ref "U16") (pin "4") (pinfunction "GND_4") (pintype "unspecified+no_connect"))
    )
    (net (code "249") (name "unconnected-(U17A-PA0-WKUP(PA0)-Pad40)") (class "Default")
      (node (ref "U17") (pin "40") (pinfunction "PA0-WKUP(PA0)_40") (pintype "unspecified+no_connect"))
    )
    (net (code "250") (name "unconnected-(U17A-PA1-Pad41)") (class "Default")
      (node (ref "U17") (pin "41") (pinfunction "PA1_41") (pintype "unspecified+no_connect"))
    )
    (net (code "251") (name "unconnected-(U17A-PA3-Pad47)") (class "Default")
      (node (ref "U17") (pin "47") (pinfunction "PA3_47") (pintype "unspecified+no_connect"))
    )
    (net (code "252") (name "unconnected-(U17A-PA4-Pad50)") (class "Default")
      (node (ref "U17") (pin "50") (pinfunction "PA4_50") (pintype "unspecified+no_connect"))
    )
    (net (code "253") (name "unconnected-(U17A-PA5-Pad51)") (class "Default")
      (node (ref "U17") (pin "51") (pinfunction "PA5_51") (pintype "unspecified+no_connect"))
    )
    (net (code "254") (name "unconnected-(U17A-PA6-Pad52)") (class "Default")
      (node (ref "U17") (pin "52") (pinfunction "PA6_52") (pintype "unspecified+no_connect"))
    )
    (net (code "255") (name "unconnected-(U17A-PA8-Pad119)") (class "Default")
      (node (ref "U17") (pin "119") (pinfunction "PA8_119") (pintype "unspecified+no_connect"))
    )
    (net (code "256") (name "unconnected-(U17A-PA9-Pad120)") (class "Default")
      (node (ref "U17") (pin "120") (pinfunction "PA9_120") (pintype "unspecified+no_connect"))
    )
    (net (code "257") (name "unconnected-(U17A-PA10-Pad121)") (class "Default")
      (node (ref "U17") (pin "121") (pinfunction "PA10_121") (pintype "unspecified+no_connect"))
    )
    (net (code "258") (name "unconnected-(U17A-PA11-Pad122)") (class "Default")
      (node (ref "U17") (pin "122") (pinfunction "PA11_122") (pintype "unspecified+no_connect"))
    )
    (net (code "259") (name "unconnected-(U17A-PA12-Pad123)") (class "Default")
      (node (ref "U17") (pin "123") (pinfunction "PA12_123") (pintype "unspecified+no_connect"))
    )
    (net (code "260") (name "unconnected-(U17A-PA15(JTDI)-Pad138)") (class "Default")
      (node (ref "U17") (pin "138") (pinfunction "PA15(JTDI)_138") (pintype "unspecified+no_connect"))
    )
    (net (code "261") (name "unconnected-(U17A-PB0-Pad56)") (class "Default")
      (node (ref "U17") (pin "56") (pinfunction "PB0_56") (pintype "unspecified+no_connect"))
    )
    (net (code "262") (name "unconnected-(U17A-PB1-Pad57)") (class "Default")
      (node (ref "U17") (pin "57") (pinfunction "PB1_57") (pintype "unspecified+no_connect"))
    )
    (net (code "263") (name "unconnected-(U17A-PB3(JTDO{slash}TRACESWO)-Pad161)") (class "Default")
      (node (ref "U17") (pin "161") (pinfunction "PB3(JTDO/TRACESWO)_161") (pintype "bidirectional+no_connect"))
    )
    (net (code "264") (name "unconnected-(U17A-PB4(NJTRST)-Pad162)") (class "Default")
      (node (ref "U17") (pin "162") (pinfunction "PB4(NJTRST)_162") (pintype "bidirectional+no_connect"))
    )
    (net (code "265") (name "unconnected-(U17A-PB5-Pad163)") (class "Default")
      (node (ref "U17") (pin "163") (pinfunction "PB5_163") (pintype "unspecified+no_connect"))
    )
    (net (code "266") (name "unconnected-(U17A-PB6-Pad164)") (class "Default")
      (node (ref "U17") (pin "164") (pinfunction "PB6_164") (pintype "unspecified+no_connect"))
    )
    (net (code "267") (name "unconnected-(U17A-PB7-Pad165)") (class "Default")
      (node (ref "U17") (pin "165") (pinfunction "PB7_165") (pintype "unspecified+no_connect"))
    )
    (net (code "268") (name "unconnected-(U17A-PB8-Pad167)") (class "Default")
      (node (ref "U17") (pin "167") (pinfunction "PB8_167") (pintype "unspecified+no_connect"))
    )
    (net (code "269") (name "unconnected-(U17A-PB9-Pad168)") (class "Default")
      (node (ref "U17") (pin "168") (pinfunction "PB9_168") (pintype "unspecified+no_connect"))
    )
    (net (code "270") (name "unconnected-(U17A-PB10-Pad79)") (class "Default")
      (node (ref "U17") (pin "79") (pinfunction "PB10_79") (pintype "unspecified+no_connect"))
    )
    (net (code "271") (name "unconnected-(U17A-PB12-Pad92)") (class "Default")
      (node (ref "U17") (pin "92") (pinfunction "PB12_92") (pintype "unspecified+no_connect"))
    )
    (net (code "272") (name "unconnected-(U17A-PB13-Pad93)") (class "Default")
      (node (ref "U17") (pin "93") (pinfunction "PB13_93") (pintype "unspecified+no_connect"))
    )
    (net (code "273") (name "unconnected-(U17A-PB14-Pad94)") (class "Default")
      (node (ref "U17") (pin "94") (pinfunction "PB14_94") (pintype "unspecified+no_connect"))
    )
    (net (code "274") (name "unconnected-(U17A-PB15-Pad95)") (class "Default")
      (node (ref "U17") (pin "95") (pinfunction "PB15_95") (pintype "unspecified+no_connect"))
    )
    (net (code "275") (name "unconnected-(U17A-PC0-Pad32)") (class "Default")
      (node (ref "U17") (pin "32") (pinfunction "PC0_32") (pintype "unspecified+no_connect"))
    )
    (net (code "276") (name "unconnected-(U17A-PC2-Pad34)") (class "Default")
      (node (ref "U17") (pin "34") (pinfunction "PC2_34") (pintype "unspecified+no_connect"))
    )
    (net (code "277") (name "unconnected-(U17A-PC3-Pad35)") (class "Default")
      (node (ref "U17") (pin "35") (pinfunction "PC3_35") (pintype "unspecified+no_connect"))
    )
    (net (code "278") (name "unconnected-(U17A-PC6-Pad115)") (class "Default")
      (node (ref "U17") (pin "115") (pinfunction "PC6_115") (pintype "unspecified+no_connect"))
    )
    (net (code "279") (name "unconnected-(U17A-PC7-Pad116)") (class "Default")
      (node (ref "U17") (pin "116") (pinfunction "PC7_116") (pintype "unspecified+no_connect"))
    )
    (net (code "280") (name "unconnected-(U17A-PD2-Pad144)") (class "Default")
      (node (ref "U17") (pin "144") (pinfunction "PD2_144") (pintype "unspecified+no_connect"))
    )
    (net (code "281") (name "unconnected-(U17A-PD3-Pad145)") (class "Default")
      (node (ref "U17") (pin "145") (pinfunction "PD3_145") (pintype "unspecified+no_connect"))
    )
    (net (code "282") (name "unconnected-(U17A-PD7-Pad151)") (class "Default")
      (node (ref "U17") (pin "151") (pinfunction "PD7_151") (pintype "unspecified+no_connect"))
    )
    (net (code "283") (name "unconnected-(U17A-PD8-Pad96)") (class "Default")
      (node (ref "U17") (pin "96") (pinfunction "PD8_96") (pintype "unspecified+no_connect"))
    )
    (net (code "284") (name "unconnected-(U17A-PD9-Pad97)") (class "Default")
      (node (ref "U17") (pin "97") (pinfunction "PD9_97") (pintype "unspecified+no_connect"))
    )
    (net (code "285") (name "unconnected-(U17A-PD10-Pad98)") (class "Default")
      (node (ref "U17") (pin "98") (pinfunction "PD10_98") (pintype "unspecified+no_connect"))
    )
    (net (code "286") (name "unconnected-(U17A-PD13-Pad101)") (class "Default")
      (node (ref "U17") (pin "101") (pinfunction "PD13_101") (pintype "unspecified+no_connect"))
    )
    (net (code "287") (name "unconnected-(U17A-PE0-Pad169)") (class "Default")
      (node (ref "U17") (pin "169") (pinfunction "PE0_169") (pintype "unspecified+no_connect"))
    )
    (net (code "288") (name "unconnected-(U17A-PE1-Pad170)") (class "Default")
      (node (ref "U17") (pin "170") (pinfunction "PE1_170") (pintype "unspecified+no_connect"))
    )
    (net (code "289") (name "unconnected-(U17A-PE4-Pad3)") (class "Default")
      (node (ref "U17") (pin "3") (pinfunction "PE4_3") (pintype "unspecified+no_connect"))
    )
    (net (code "290") (name "unconnected-(U17A-PE5-Pad4)") (class "Default")
      (node (ref "U17") (pin "4") (pinfunction "PE5_4") (pintype "unspecified+no_connect"))
    )
    (net (code "291") (name "unconnected-(U17A-PE6-Pad5)") (class "Default")
      (node (ref "U17") (pin "5") (pinfunction "PE6_5") (pintype "unspecified+no_connect"))
    )
    (net (code "292") (name "unconnected-(U17A-PE11-Pad74)") (class "Default")
      (node (ref "U17") (pin "74") (pinfunction "PE11_74") (pintype "unspecified+no_connect"))
    )
    (net (code "293") (name "unconnected-(U17A-PE12-Pad75)") (class "Default")
      (node (ref "U17") (pin "75") (pinfunction "PE12_75") (pintype "unspecified+no_connect"))
    )
    (net (code "294") (name "unconnected-(U17A-PE13-Pad76)") (class "Default")
      (node (ref "U17") (pin "76") (pinfunction "PE13_76") (pintype "unspecified+no_connect"))
    )
    (net (code "295") (name "unconnected-(U17A-PE14-Pad77)") (class "Default")
      (node (ref "U17") (pin "77") (pinfunction "PE14_77") (pintype "unspecified+no_connect"))
    )
    (net (code "296") (name "unconnected-(U17A-PE15-Pad78)") (class "Default")
      (node (ref "U17") (pin "78") (pinfunction "PE15_78") (pintype "unspecified+no_connect"))
    )
    (net (code "297") (name "unconnected-(U17A-PF11-Pad59)") (class "Default")
      (node (ref "U17") (pin "59") (pinfunction "PF11_59") (pintype "unspecified+no_connect"))
    )
    (net (code "298") (name "unconnected-(U17A-PF12-Pad60)") (class "Default")
      (node (ref "U17") (pin "60") (pinfunction "PF12_60") (pintype "unspecified+no_connect"))
    )
    (net (code "299") (name "unconnected-(U17A-PF13-Pad63)") (class "Default")
      (node (ref "U17") (pin "63") (pinfunction "PF13_63") (pintype "unspecified+no_connect"))
    )
    (net (code "300") (name "unconnected-(U17A-PF14-Pad64)") (class "Default")
      (node (ref "U17") (pin "64") (pinfunction "PF14_64") (pintype "unspecified+no_connect"))
    )
    (net (code "301") (name "unconnected-(U17A-PF15-Pad65)") (class "Default")
      (node (ref "U17") (pin "65") (pinfunction "PF15_65") (pintype "unspecified+no_connect"))
    )
    (net (code "302") (name "unconnected-(U17B-PG0-Pad66)") (class "Default")
      (node (ref "U17") (pin "66") (pinfunction "PG0_66") (pintype "unspecified+no_connect"))
    )
    (net (code "303") (name "unconnected-(U17B-PG1-Pad67)") (class "Default")
      (node (ref "U17") (pin "67") (pinfunction "PG1_67") (pintype "unspecified+no_connect"))
    )
    (net (code "304") (name "unconnected-(U17B-PG2-Pad106)") (class "Default")
      (node (ref "U17") (pin "106") (pinfunction "PG2_106") (pintype "unspecified+no_connect"))
    )
    (net (code "305") (name "unconnected-(U17B-PG3-Pad107)") (class "Default")
      (node (ref "U17") (pin "107") (pinfunction "PG3_107") (pintype "unspecified+no_connect"))
    )
    (net (code "306") (name "unconnected-(U17B-PG4-Pad108)") (class "Default")
      (node (ref "U17") (pin "108") (pinfunction "PG4_108") (pintype "unspecified+no_connect"))
    )
    (net (code "307") (name "unconnected-(U17B-PG5-Pad109)") (class "Default")
      (node (ref "U17") (pin "109") (pinfunction "PG5_109") (pintype "unspecified+no_connect"))
    )
    (net (code "308") (name "unconnected-(U17B-PG6-Pad110)") (class "Default")
      (node (ref "U17") (pin "110") (pinfunction "PG6_110") (pintype "unspecified+no_connect"))
    )
    (net (code "309") (name "unconnected-(U17B-PG7-Pad111)") (class "Default")
      (node (ref "U17") (pin "111") (pinfunction "PG7_111") (pintype "unspecified+no_connect"))
    )
    (net (code "310") (name "unconnected-(U17B-PG8-Pad112)") (class "Default")
      (node (ref "U17") (pin "112") (pinfunction "PG8_112") (pintype "unspecified+no_connect"))
    )
    (net (code "311") (name "unconnected-(U17B-PG10-Pad153)") (class "Default")
      (node (ref "U17") (pin "153") (pinfunction "PG10_153") (pintype "unspecified+no_connect"))
    )
    (net (code "312") (name "unconnected-(U17B-PG11-Pad154)") (class "Default")
      (node (ref "U17") (pin "154") (pinfunction "PG11_154") (pintype "unspecified+no_connect"))
    )
    (net (code "313") (name "unconnected-(U17B-PG12-Pad155)") (class "Default")
      (node (ref "U17") (pin "155") (pinfunction "PG12_155") (pintype "unspecified+no_connect"))
    )
    (net (code "314") (name "unconnected-(U17B-PG15-Pad160)") (class "Default")
      (node (ref "U17") (pin "160") (pinfunction "PG15_160") (pintype "unspecified+no_connect"))
    )
    (net (code "315") (name "unconnected-(U17B-PH2-Pad43)") (class "Default")
      (node (ref "U17") (pin "43") (pinfunction "PH2_43") (pintype "unspecified+no_connect"))
    )
    (net (code "316") (name "unconnected-(U17B-PH3-Pad44)") (class "Default")
      (node (ref "U17") (pin "44") (pinfunction "PH3_44") (pintype "unspecified+no_connect"))
    )
    (net (code "317") (name "unconnected-(U17B-PH6-Pad83)") (class "Default")
      (node (ref "U17") (pin "83") (pinfunction "PH6_83") (pintype "unspecified+no_connect"))
    )
    (net (code "318") (name "unconnected-(U17B-PH7-Pad84)") (class "Default")
      (node (ref "U17") (pin "84") (pinfunction "PH7_84") (pintype "unspecified+no_connect"))
    )
    (net (code "319") (name "unconnected-(U17B-PH8-Pad85)") (class "Default")
      (node (ref "U17") (pin "85") (pinfunction "PH8_85") (pintype "unspecified+no_connect"))
    )
    (net (code "320") (name "unconnected-(U17B-PH9-Pad86)") (class "Default")
      (node (ref "U17") (pin "86") (pinfunction "PH9_86") (pintype "unspecified+no_connect"))
    )
    (net (code "321") (name "unconnected-(U17B-PH10-Pad87)") (class "Default")
      (node (ref "U17") (pin "87") (pinfunction "PH10_87") (pintype "unspecified+no_connect"))
    )
    (net (code "322") (name "unconnected-(U17B-PH11-Pad88)") (class "Default")
      (node (ref "U17") (pin "88") (pinfunction "PH11_88") (pintype "unspecified+no_connect"))
    )
    (net (code "323") (name "unconnected-(U17B-PH12-Pad89)") (class "Default")
      (node (ref "U17") (pin "89") (pinfunction "PH12_89") (pintype "unspecified+no_connect"))
    )
    (net (code "324") (name "unconnected-(U17B-PH13-Pad128)") (class "Default")
      (node (ref "U17") (pin "128") (pinfunction "PH13_128") (pintype "unspecified+no_connect"))
    )
    (net (code "325") (name "unconnected-(U17B-PH14-Pad129)") (class "Default")
      (node (ref "U17") (pin "129") (pinfunction "PH14_129") (pintype "unspecified+no_connect"))
    )
    (net (code "326") (name "unconnected-(U17B-PH15-Pad130)") (class "Default")
      (node (ref "U17") (pin "130") (pinfunction "PH15_130") (pintype "unspecified+no_connect"))
    )
    (net (code "327") (name "unconnected-(U17B-PI0-Pad131)") (class "Default")
      (node (ref "U17") (pin "131") (pinfunction "PI0_131") (pintype "unspecified+no_connect"))
    )
    (net (code "328") (name "unconnected-(U17B-PI1-Pad132)") (class "Default")
      (node (ref "U17") (pin "132") (pinfunction "PI1_132") (pintype "unspecified+no_connect"))
    )
    (net (code "329") (name "unconnected-(U17B-PI2-Pad133)") (class "Default")
      (node (ref "U17") (pin "133") (pinfunction "PI2_133") (pintype "unspecified+no_connect"))
    )
    (net (code "330") (name "unconnected-(U17B-PI3-Pad134)") (class "Default")
      (node (ref "U17") (pin "134") (pinfunction "PI3_134") (pintype "unspecified+no_connect"))
    )
    (net (code "331") (name "unconnected-(U17B-PI8-Pad7)") (class "Default")
      (node (ref "U17") (pin "7") (pinfunction "PI8_7") (pintype "unspecified+no_connect"))
    )
    (net (code "332") (name "unconnected-(U17B-PI9-Pad11)") (class "Default")
      (node (ref "U17") (pin "11") (pinfunction "PI9_11") (pintype "unspecified+no_connect"))
    )
    (net (code "333") (name "unconnected-(U17B-PI10-Pad12)") (class "Default")
      (node (ref "U17") (pin "12") (pinfunction "PI10_12") (pintype "unspecified+no_connect"))
    )
    (net (code "334") (name "unconnected-(U17B-PI11-Pad13)") (class "Default")
      (node (ref "U17") (pin "13") (pinfunction "PI11_13") (pintype "unspecified+no_connect"))
    )
    (net (code "335") (name "unconnected-(U17C-VBAT-Pad6)") (class "Default")
      (node (ref "U17") (pin "6") (pinfunction "VBAT_6") (pintype "unspecified+no_connect"))
    )
  )
)
